# LED_INDICATORS.net
KiCad netlist of a schematic drawn in Altium Designer
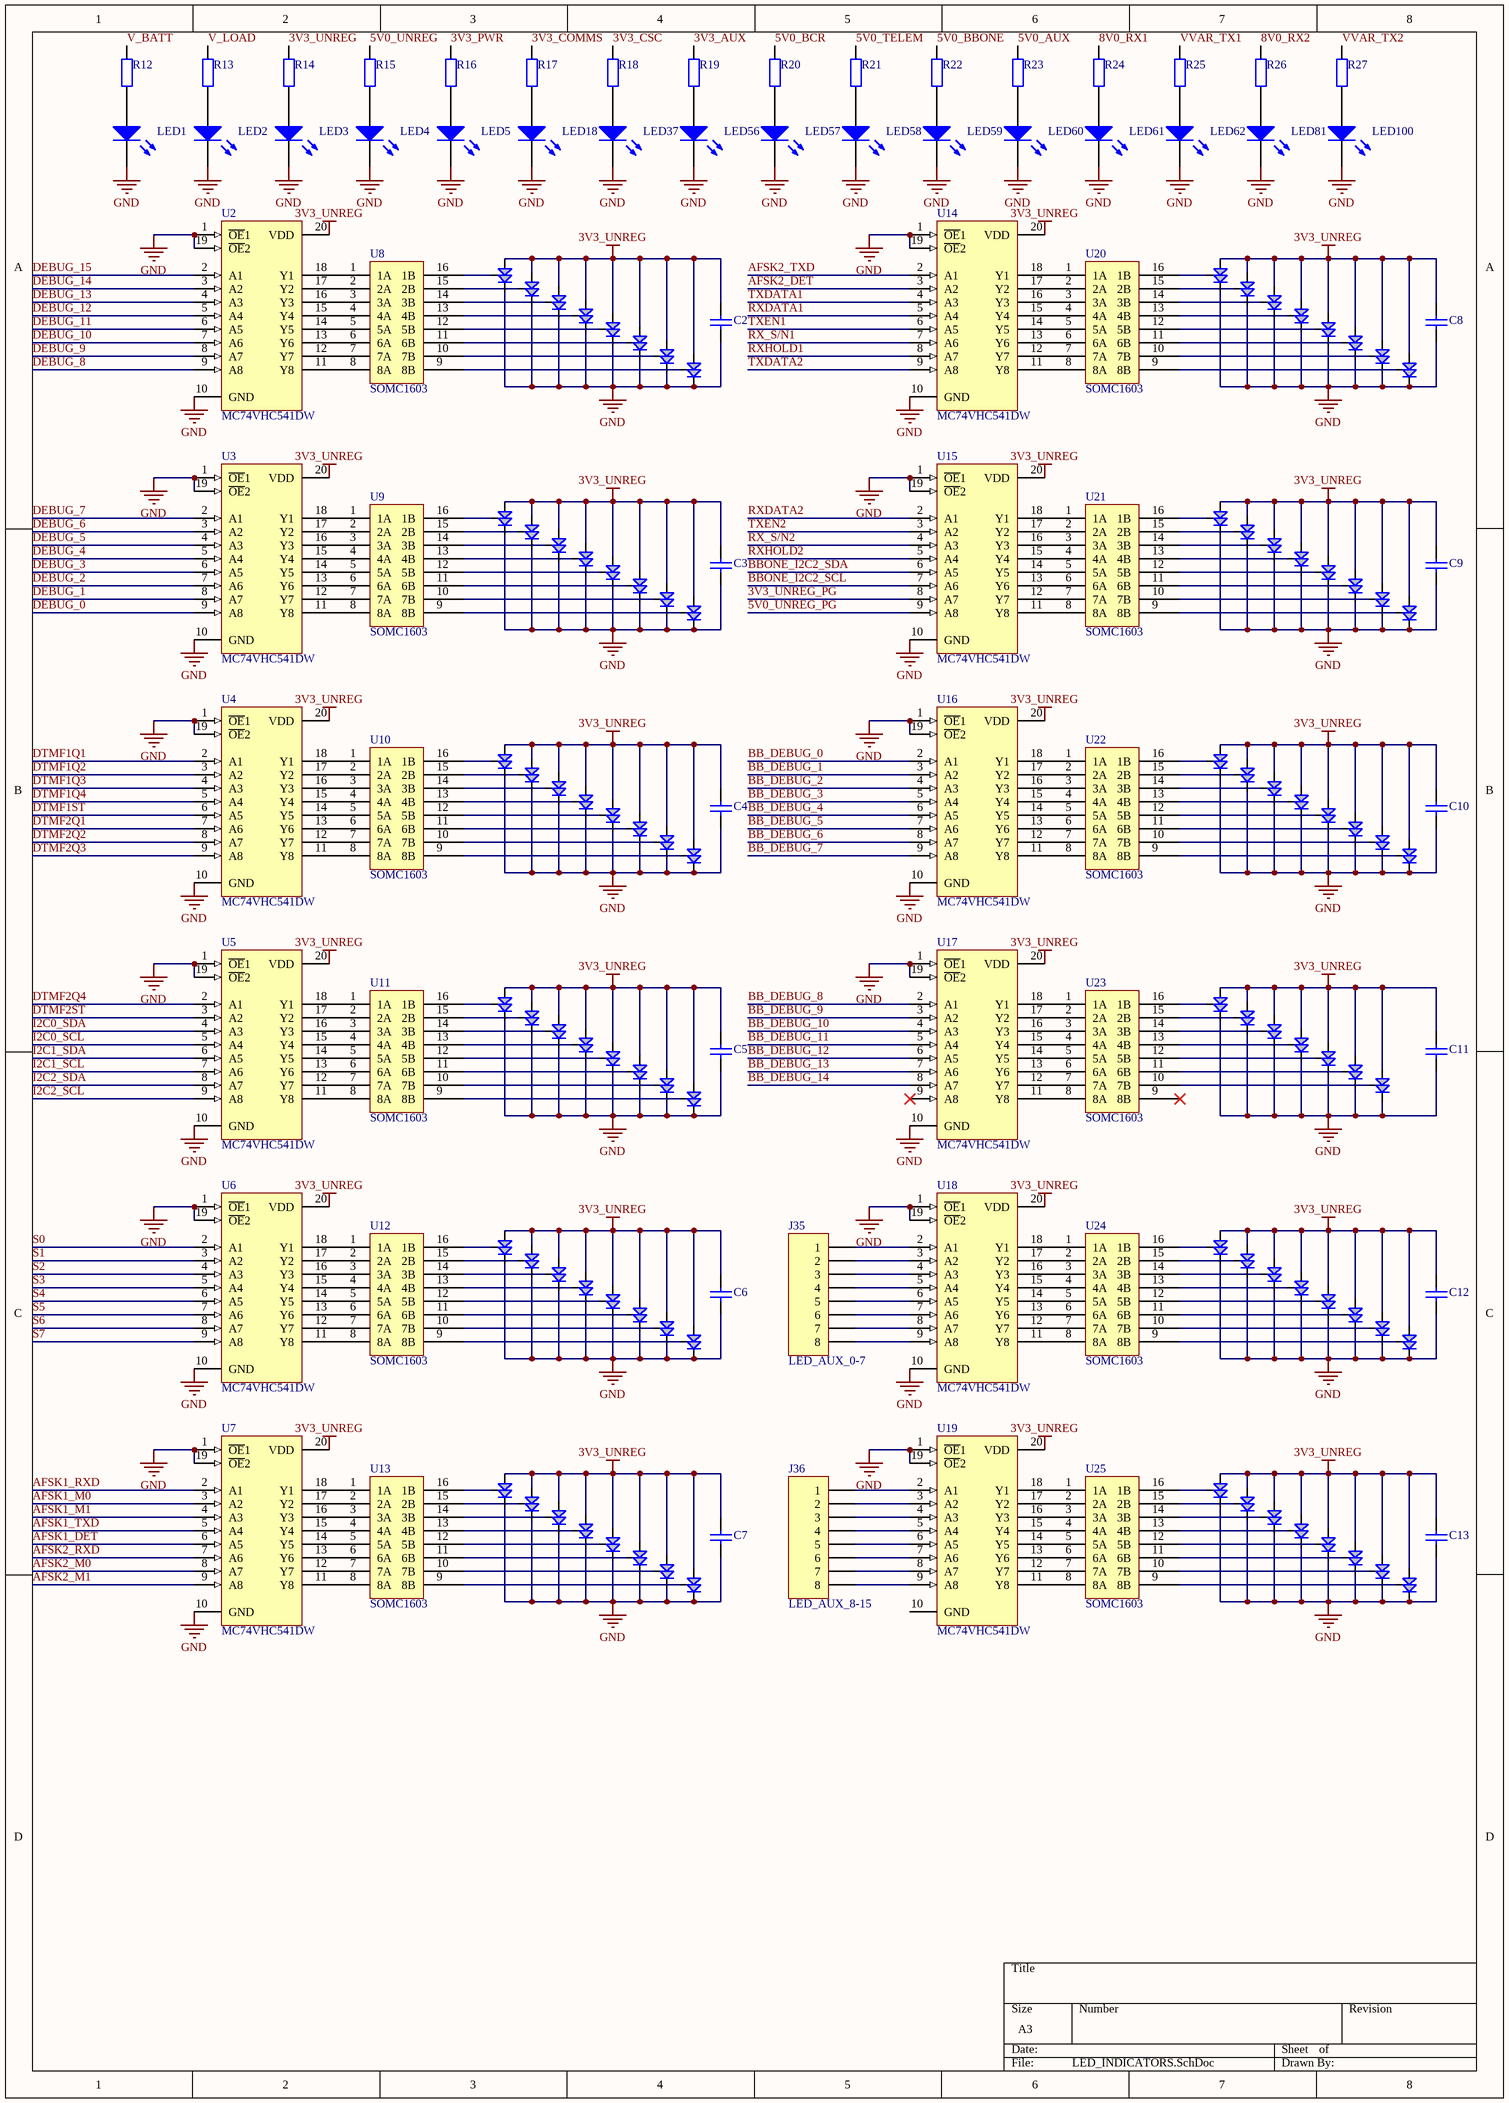
[diagram p0: LED_INDICATORS.SchDoc]

(export (version "E")
  (design (tool "Eeschema 10.0.6"))
  (components
    (comp (ref "C2")
      (value "~")
      (footprint "6-0805_M")
      (description "Capacitor")
      (fields (field (name "PUBLISHER") "Altium Limited"))
      (libsource (lib "Miscellaneous Devices") (part "Cap"))
    )
    (comp (ref "C3")
      (value "~")
      (footprint "6-0805_M")
      (description "Capacitor")
      (fields (field (name "PUBLISHER") "Altium Limited"))
      (libsource (lib "Miscellaneous Devices") (part "Cap"))
    )
    (comp (ref "C4")
      (value "~")
      (footprint "6-0805_M")
      (description "Capacitor")
      (fields (field (name "PUBLISHER") "Altium Limited"))
      (libsource (lib "Miscellaneous Devices") (part "Cap"))
    )
    (comp (ref "C5")
      (value "~")
      (footprint "6-0805_M")
      (description "Capacitor")
      (fields (field (name "PUBLISHER") "Altium Limited"))
      (libsource (lib "Miscellaneous Devices") (part "Cap"))
    )
    (comp (ref "C6")
      (value "~")
      (footprint "6-0805_M")
      (description "Capacitor")
      (fields (field (name "PUBLISHER") "Altium Limited"))
      (libsource (lib "Miscellaneous Devices") (part "Cap"))
    )
    (comp (ref "C7")
      (value "~")
      (footprint "6-0805_M")
      (description "Capacitor")
      (fields (field (name "PUBLISHER") "Altium Limited"))
      (libsource (lib "Miscellaneous Devices") (part "Cap"))
    )
    (comp (ref "C8")
      (value "~")
      (footprint "6-0805_M")
      (description "Capacitor")
      (fields (field (name "PUBLISHER") "Altium Limited"))
      (libsource (lib "Miscellaneous Devices") (part "Cap"))
    )
    (comp (ref "C9")
      (value "~")
      (footprint "6-0805_M")
      (description "Capacitor")
      (fields (field (name "PUBLISHER") "Altium Limited"))
      (libsource (lib "Miscellaneous Devices") (part "Cap"))
    )
    (comp (ref "C10")
      (value "~")
      (footprint "6-0805_M")
      (description "Capacitor")
      (fields (field (name "PUBLISHER") "Altium Limited"))
      (libsource (lib "Miscellaneous Devices") (part "Cap"))
    )
    (comp (ref "C11")
      (value "~")
      (footprint "6-0805_M")
      (description "Capacitor")
      (fields (field (name "PUBLISHER") "Altium Limited"))
      (libsource (lib "Miscellaneous Devices") (part "Cap"))
    )
    (comp (ref "C12")
      (value "~")
      (footprint "6-0805_M")
      (description "Capacitor")
      (fields (field (name "PUBLISHER") "Altium Limited"))
      (libsource (lib "Miscellaneous Devices") (part "Cap"))
    )
    (comp (ref "C13")
      (value "~")
      (footprint "6-0805_M")
      (description "Capacitor")
      (fields (field (name "PUBLISHER") "Altium Limited"))
      (libsource (lib "Miscellaneous Devices") (part "Cap"))
    )
    (comp (ref "J35")
      (value "LED_AUX_0-7")
      (footprint "HDR1X8")
      (description "Header, 8-Pin")
      (fields (field (name "PUBLISHER") "Altium Limited"))
      (libsource (lib "Miscellaneous Connectors") (part "Header 8"))
    )
    (comp (ref "J36")
      (value "LED_AUX_8-15")
      (footprint "HDR1X8")
      (description "Header, 8-Pin")
      (fields (field (name "PUBLISHER") "Altium Limited"))
      (libsource (lib "Miscellaneous Connectors") (part "Header 8"))
    )
    (comp (ref "LED1")
      (value "V_BATT")
      (footprint "6-0805_M")
      (description "Typical INFRARED GaAs LED")
      (fields (field (name "PUBLISHER") "Altium Limited"))
      (libsource (lib "Miscellaneous Devices") (part "LED0"))
    )
    (comp (ref "LED2")
      (value "V_LOAD")
      (footprint "6-0805_M")
      (description "Typical INFRARED GaAs LED")
      (fields (field (name "PUBLISHER") "Altium Limited"))
      (libsource (lib "Miscellaneous Devices") (part "LED0"))
    )
    (comp (ref "LED3")
      (value "3V3_UNREG")
      (footprint "6-0805_M")
      (description "Typical INFRARED GaAs LED")
      (fields (field (name "PUBLISHER") "Altium Limited"))
      (libsource (lib "Miscellaneous Devices") (part "LED0"))
    )
    (comp (ref "LED4")
      (value "5V0_UNREG")
      (footprint "6-0805_M")
      (description "Typical INFRARED GaAs LED")
      (fields (field (name "PUBLISHER") "Altium Limited"))
      (libsource (lib "Miscellaneous Devices") (part "LED0"))
    )
    (comp (ref "LED5")
      (value "3V3_PWR")
      (footprint "6-0805_M")
      (description "Typical INFRARED GaAs LED")
      (fields (field (name "PUBLISHER") "Altium Limited"))
      (libsource (lib "Miscellaneous Devices") (part "LED0"))
    )
    (comp (ref "LED6")
      (value "DEBUG_15")
      (footprint "BIDIRECTIONAL LED")
      (libsource (lib "FlatBoards") (part "BIDIRECTIONAL LED"))
    )
    (comp (ref "LED7")
      (value "DEBUG_7")
      (footprint "BIDIRECTIONAL LED")
      (libsource (lib "FlatBoards") (part "BIDIRECTIONAL LED"))
    )
    (comp (ref "LED8")
      (value "DTMF1Q1")
      (footprint "BIDIRECTIONAL LED")
      (libsource (lib "FlatBoards") (part "BIDIRECTIONAL LED"))
    )
    (comp (ref "LED9")
      (value "DTMF2Q4")
      (footprint "BIDIRECTIONAL LED")
      (libsource (lib "FlatBoards") (part "BIDIRECTIONAL LED"))
    )
    (comp (ref "LED10")
      (value "S0")
      (footprint "BIDIRECTIONAL LED")
      (libsource (lib "FlatBoards") (part "BIDIRECTIONAL LED"))
    )
    (comp (ref "LED11")
      (value "AFSK1_RXD")
      (footprint "BIDIRECTIONAL LED")
      (libsource (lib "FlatBoards") (part "BIDIRECTIONAL LED"))
    )
    (comp (ref "LED12")
      (value "DEBUG_14")
      (footprint "BIDIRECTIONAL LED")
      (libsource (lib "FlatBoards") (part "BIDIRECTIONAL LED"))
    )
    (comp (ref "LED13")
      (value "DEBUG_6")
      (footprint "BIDIRECTIONAL LED")
      (libsource (lib "FlatBoards") (part "BIDIRECTIONAL LED"))
    )
    (comp (ref "LED14")
      (value "DTMF1Q2")
      (footprint "BIDIRECTIONAL LED")
      (libsource (lib "FlatBoards") (part "BIDIRECTIONAL LED"))
    )
    (comp (ref "LED15")
      (value "DTMF2ST")
      (footprint "BIDIRECTIONAL LED")
      (libsource (lib "FlatBoards") (part "BIDIRECTIONAL LED"))
    )
    (comp (ref "LED16")
      (value "S1")
      (footprint "BIDIRECTIONAL LED")
      (libsource (lib "FlatBoards") (part "BIDIRECTIONAL LED"))
    )
    (comp (ref "LED17")
      (value "AFSK1_M0")
      (footprint "BIDIRECTIONAL LED")
      (libsource (lib "FlatBoards") (part "BIDIRECTIONAL LED"))
    )
    (comp (ref "LED18")
      (value "3V3_COMMS")
      (footprint "6-0805_M")
      (description "Typical INFRARED GaAs LED")
      (fields (field (name "PUBLISHER") "Altium Limited"))
      (libsource (lib "Miscellaneous Devices") (part "LED0"))
    )
    (comp (ref "LED19")
      (value "DEBUG_13")
      (footprint "BIDIRECTIONAL LED")
      (libsource (lib "FlatBoards") (part "BIDIRECTIONAL LED"))
    )
    (comp (ref "LED20")
      (value "DEBUG_5")
      (footprint "BIDIRECTIONAL LED")
      (libsource (lib "FlatBoards") (part "BIDIRECTIONAL LED"))
    )
    (comp (ref "LED21")
      (value "DTMF1Q3")
      (footprint "BIDIRECTIONAL LED")
      (libsource (lib "FlatBoards") (part "BIDIRECTIONAL LED"))
    )
    (comp (ref "LED22")
      (value "I2C0_SDA")
      (footprint "BIDIRECTIONAL LED")
      (libsource (lib "FlatBoards") (part "BIDIRECTIONAL LED"))
    )
    (comp (ref "LED23")
      (value "S2")
      (footprint "BIDIRECTIONAL LED")
      (libsource (lib "FlatBoards") (part "BIDIRECTIONAL LED"))
    )
    (comp (ref "LED24")
      (value "AFSK1_M1")
      (footprint "BIDIRECTIONAL LED")
      (libsource (lib "FlatBoards") (part "BIDIRECTIONAL LED"))
    )
    (comp (ref "LED25")
      (value "DEBUG_12")
      (footprint "BIDIRECTIONAL LED")
      (libsource (lib "FlatBoards") (part "BIDIRECTIONAL LED"))
    )
    (comp (ref "LED26")
      (value "DEBUG_4")
      (footprint "BIDIRECTIONAL LED")
      (libsource (lib "FlatBoards") (part "BIDIRECTIONAL LED"))
    )
    (comp (ref "LED27")
      (value "DTMF1Q4")
      (footprint "BIDIRECTIONAL LED")
      (libsource (lib "FlatBoards") (part "BIDIRECTIONAL LED"))
    )
    (comp (ref "LED28")
      (value "I2C0_SCL")
      (footprint "BIDIRECTIONAL LED")
      (libsource (lib "FlatBoards") (part "BIDIRECTIONAL LED"))
    )
    (comp (ref "LED29")
      (value "S3")
      (footprint "BIDIRECTIONAL LED")
      (libsource (lib "FlatBoards") (part "BIDIRECTIONAL LED"))
    )
    (comp (ref "LED30")
      (value "AFSK1_TXD")
      (footprint "BIDIRECTIONAL LED")
      (libsource (lib "FlatBoards") (part "BIDIRECTIONAL LED"))
    )
    (comp (ref "LED31")
      (value "DEBUG_11")
      (footprint "BIDIRECTIONAL LED")
      (libsource (lib "FlatBoards") (part "BIDIRECTIONAL LED"))
    )
    (comp (ref "LED32")
      (value "DEBUG_3")
      (footprint "BIDIRECTIONAL LED")
      (libsource (lib "FlatBoards") (part "BIDIRECTIONAL LED"))
    )
    (comp (ref "LED33")
      (value "DTMF1ST")
      (footprint "BIDIRECTIONAL LED")
      (libsource (lib "FlatBoards") (part "BIDIRECTIONAL LED"))
    )
    (comp (ref "LED34")
      (value "I2C1_SDA")
      (footprint "BIDIRECTIONAL LED")
      (libsource (lib "FlatBoards") (part "BIDIRECTIONAL LED"))
    )
    (comp (ref "LED35")
      (value "S4")
      (footprint "BIDIRECTIONAL LED")
      (libsource (lib "FlatBoards") (part "BIDIRECTIONAL LED"))
    )
    (comp (ref "LED36")
      (value "AFSK1_DET")
      (footprint "BIDIRECTIONAL LED")
      (libsource (lib "FlatBoards") (part "BIDIRECTIONAL LED"))
    )
    (comp (ref "LED37")
      (value "3V3_CSC")
      (footprint "6-0805_M")
      (description "Typical INFRARED GaAs LED")
      (fields (field (name "PUBLISHER") "Altium Limited"))
      (libsource (lib "Miscellaneous Devices") (part "LED0"))
    )
    (comp (ref "LED38")
      (value "DEBUG_10")
      (footprint "BIDIRECTIONAL LED")
      (libsource (lib "FlatBoards") (part "BIDIRECTIONAL LED"))
    )
    (comp (ref "LED39")
      (value "DEBUG_2")
      (footprint "BIDIRECTIONAL LED")
      (libsource (lib "FlatBoards") (part "BIDIRECTIONAL LED"))
    )
    (comp (ref "LED40")
      (value "DTMF2Q1")
      (footprint "BIDIRECTIONAL LED")
      (libsource (lib "FlatBoards") (part "BIDIRECTIONAL LED"))
    )
    (comp (ref "LED41")
      (value "I2C1_SCL")
      (footprint "BIDIRECTIONAL LED")
      (libsource (lib "FlatBoards") (part "BIDIRECTIONAL LED"))
    )
    (comp (ref "LED42")
      (value "S5")
      (footprint "BIDIRECTIONAL LED")
      (libsource (lib "FlatBoards") (part "BIDIRECTIONAL LED"))
    )
    (comp (ref "LED43")
      (value "AFSK2_RXD")
      (footprint "BIDIRECTIONAL LED")
      (libsource (lib "FlatBoards") (part "BIDIRECTIONAL LED"))
    )
    (comp (ref "LED44")
      (value "DEBUG_9")
      (footprint "BIDIRECTIONAL LED")
      (libsource (lib "FlatBoards") (part "BIDIRECTIONAL LED"))
    )
    (comp (ref "LED45")
      (value "DEBUG_1")
      (footprint "BIDIRECTIONAL LED")
      (libsource (lib "FlatBoards") (part "BIDIRECTIONAL LED"))
    )
    (comp (ref "LED46")
      (value "DTMF2Q2")
      (footprint "BIDIRECTIONAL LED")
      (libsource (lib "FlatBoards") (part "BIDIRECTIONAL LED"))
    )
    (comp (ref "LED47")
      (value "I2C2_SDA")
      (footprint "BIDIRECTIONAL LED")
      (libsource (lib "FlatBoards") (part "BIDIRECTIONAL LED"))
    )
    (comp (ref "LED48")
      (value "S6")
      (footprint "BIDIRECTIONAL LED")
      (libsource (lib "FlatBoards") (part "BIDIRECTIONAL LED"))
    )
    (comp (ref "LED49")
      (value "AFSK2_M0")
      (footprint "BIDIRECTIONAL LED")
      (libsource (lib "FlatBoards") (part "BIDIRECTIONAL LED"))
    )
    (comp (ref "LED50")
      (value "DEBUG_8")
      (footprint "BIDIRECTIONAL LED")
      (libsource (lib "FlatBoards") (part "BIDIRECTIONAL LED"))
    )
    (comp (ref "LED51")
      (value "DEBUG_0")
      (footprint "BIDIRECTIONAL LED")
      (libsource (lib "FlatBoards") (part "BIDIRECTIONAL LED"))
    )
    (comp (ref "LED52")
      (value "DTMF2Q3")
      (footprint "BIDIRECTIONAL LED")
      (libsource (lib "FlatBoards") (part "BIDIRECTIONAL LED"))
    )
    (comp (ref "LED53")
      (value "I2C2_SCL")
      (footprint "BIDIRECTIONAL LED")
      (libsource (lib "FlatBoards") (part "BIDIRECTIONAL LED"))
    )
    (comp (ref "LED54")
      (value "S7")
      (footprint "BIDIRECTIONAL LED")
      (libsource (lib "FlatBoards") (part "BIDIRECTIONAL LED"))
    )
    (comp (ref "LED55")
      (value "AFSK2_M1")
      (footprint "BIDIRECTIONAL LED")
      (libsource (lib "FlatBoards") (part "BIDIRECTIONAL LED"))
    )
    (comp (ref "LED56")
      (value "3V3_AUX")
      (footprint "6-0805_M")
      (description "Typical INFRARED GaAs LED")
      (fields (field (name "PUBLISHER") "Altium Limited"))
      (libsource (lib "Miscellaneous Devices") (part "LED0"))
    )
    (comp (ref "LED57")
      (value "5V0_BCR")
      (footprint "6-0805_M")
      (description "Typical INFRARED GaAs LED")
      (fields (field (name "PUBLISHER") "Altium Limited"))
      (libsource (lib "Miscellaneous Devices") (part "LED0"))
    )
    (comp (ref "LED58")
      (value "5V0_TELEM")
      (footprint "6-0805_M")
      (description "Typical INFRARED GaAs LED")
      (fields (field (name "PUBLISHER") "Altium Limited"))
      (libsource (lib "Miscellaneous Devices") (part "LED0"))
    )
    (comp (ref "LED59")
      (value "5V0_BBONE")
      (footprint "6-0805_M")
      (description "Typical INFRARED GaAs LED")
      (fields (field (name "PUBLISHER") "Altium Limited"))
      (libsource (lib "Miscellaneous Devices") (part "LED0"))
    )
    (comp (ref "LED60")
      (value "5V0_AUX")
      (footprint "6-0805_M")
      (description "Typical INFRARED GaAs LED")
      (fields (field (name "PUBLISHER") "Altium Limited"))
      (libsource (lib "Miscellaneous Devices") (part "LED0"))
    )
    (comp (ref "LED61")
      (value "8V0_RX1")
      (footprint "6-0805_M")
      (description "Typical INFRARED GaAs LED")
      (fields (field (name "PUBLISHER") "Altium Limited"))
      (libsource (lib "Miscellaneous Devices") (part "LED0"))
    )
    (comp (ref "LED62")
      (value "VVAR_TX1")
      (footprint "6-0805_M")
      (description "Typical INFRARED GaAs LED")
      (fields (field (name "PUBLISHER") "Altium Limited"))
      (libsource (lib "Miscellaneous Devices") (part "LED0"))
    )
    (comp (ref "LED63")
      (value "AFSK2_TXD")
      (footprint "BIDIRECTIONAL LED")
      (libsource (lib "FlatBoards") (part "BIDIRECTIONAL LED"))
    )
    (comp (ref "LED64")
      (value "RXDATA2")
      (footprint "BIDIRECTIONAL LED")
      (libsource (lib "FlatBoards") (part "BIDIRECTIONAL LED"))
    )
    (comp (ref "LED65")
      (value "BB_DEBUG_0")
      (footprint "BIDIRECTIONAL LED")
      (libsource (lib "FlatBoards") (part "BIDIRECTIONAL LED"))
    )
    (comp (ref "LED66")
      (value "BB_DEBUG_8")
      (footprint "BIDIRECTIONAL LED")
      (libsource (lib "FlatBoards") (part "BIDIRECTIONAL LED"))
    )
    (comp (ref "LED67")
      (value "LED_AUX_0")
      (footprint "BIDIRECTIONAL LED")
      (libsource (lib "FlatBoards") (part "BIDIRECTIONAL LED"))
    )
    (comp (ref "LED68")
      (value "LED_AUX_8")
      (footprint "BIDIRECTIONAL LED")
      (libsource (lib "FlatBoards") (part "BIDIRECTIONAL LED"))
    )
    (comp (ref "LED69")
      (value "AFSK2_DET")
      (footprint "BIDIRECTIONAL LED")
      (libsource (lib "FlatBoards") (part "BIDIRECTIONAL LED"))
    )
    (comp (ref "LED70")
      (value "TXEN2")
      (footprint "BIDIRECTIONAL LED")
      (libsource (lib "FlatBoards") (part "BIDIRECTIONAL LED"))
    )
    (comp (ref "LED71")
      (value "BB_DEBUG_1")
      (footprint "BIDIRECTIONAL LED")
      (libsource (lib "FlatBoards") (part "BIDIRECTIONAL LED"))
    )
    (comp (ref "LED72")
      (value "BB_DEBUG_9")
      (footprint "BIDIRECTIONAL LED")
      (libsource (lib "FlatBoards") (part "BIDIRECTIONAL LED"))
    )
    (comp (ref "LED73")
      (value "LED_AUX_1")
      (footprint "BIDIRECTIONAL LED")
      (libsource (lib "FlatBoards") (part "BIDIRECTIONAL LED"))
    )
    (comp (ref "LED74")
      (value "LED_AUX_9")
      (footprint "BIDIRECTIONAL LED")
      (libsource (lib "FlatBoards") (part "BIDIRECTIONAL LED"))
    )
    (comp (ref "LED75")
      (value "TXDATA1")
      (footprint "BIDIRECTIONAL LED")
      (libsource (lib "FlatBoards") (part "BIDIRECTIONAL LED"))
    )
    (comp (ref "LED76")
      (value "RX_S/N2")
      (footprint "BIDIRECTIONAL LED")
      (libsource (lib "FlatBoards") (part "BIDIRECTIONAL LED"))
    )
    (comp (ref "LED77")
      (value "BB_DEBUG_2")
      (footprint "BIDIRECTIONAL LED")
      (libsource (lib "FlatBoards") (part "BIDIRECTIONAL LED"))
    )
    (comp (ref "LED78")
      (value "BB_DEBUG_10")
      (footprint "BIDIRECTIONAL LED")
      (libsource (lib "FlatBoards") (part "BIDIRECTIONAL LED"))
    )
    (comp (ref "LED79")
      (value "LED_AUX_2")
      (footprint "BIDIRECTIONAL LED")
      (libsource (lib "FlatBoards") (part "BIDIRECTIONAL LED"))
    )
    (comp (ref "LED80")
      (value "LED_AUX_10")
      (footprint "BIDIRECTIONAL LED")
      (libsource (lib "FlatBoards") (part "BIDIRECTIONAL LED"))
    )
    (comp (ref "LED81")
      (value "8V0_RX2")
      (footprint "6-0805_M")
      (description "Typical INFRARED GaAs LED")
      (fields (field (name "PUBLISHER") "Altium Limited"))
      (libsource (lib "Miscellaneous Devices") (part "LED0"))
    )
    (comp (ref "LED82")
      (value "RXDATA1")
      (footprint "BIDIRECTIONAL LED")
      (libsource (lib "FlatBoards") (part "BIDIRECTIONAL LED"))
    )
    (comp (ref "LED83")
      (value "RXHOLD2")
      (footprint "BIDIRECTIONAL LED")
      (libsource (lib "FlatBoards") (part "BIDIRECTIONAL LED"))
    )
    (comp (ref "LED84")
      (value "BB_DEBUG_3")
      (footprint "BIDIRECTIONAL LED")
      (libsource (lib "FlatBoards") (part "BIDIRECTIONAL LED"))
    )
    (comp (ref "LED85")
      (value "BB_DEBUG_11")
      (footprint "BIDIRECTIONAL LED")
      (libsource (lib "FlatBoards") (part "BIDIRECTIONAL LED"))
    )
    (comp (ref "LED86")
      (value "LED_AUX_3")
      (footprint "BIDIRECTIONAL LED")
      (libsource (lib "FlatBoards") (part "BIDIRECTIONAL LED"))
    )
    (comp (ref "LED87")
      (value "LED_AUX_11")
      (footprint "BIDIRECTIONAL LED")
      (libsource (lib "FlatBoards") (part "BIDIRECTIONAL LED"))
    )
    (comp (ref "LED88")
      (value "TXEN1")
      (footprint "BIDIRECTIONAL LED")
      (libsource (lib "FlatBoards") (part "BIDIRECTIONAL LED"))
    )
    (comp (ref "LED89")
      (value "BBONE_I2C2_SDA")
      (footprint "BIDIRECTIONAL LED")
      (libsource (lib "FlatBoards") (part "BIDIRECTIONAL LED"))
    )
    (comp (ref "LED90")
      (value "BB_DEBUG_4")
      (footprint "BIDIRECTIONAL LED")
      (libsource (lib "FlatBoards") (part "BIDIRECTIONAL LED"))
    )
    (comp (ref "LED91")
      (value "BB_DEBUG_12")
      (footprint "BIDIRECTIONAL LED")
      (libsource (lib "FlatBoards") (part "BIDIRECTIONAL LED"))
    )
    (comp (ref "LED92")
      (value "LED_AUX_4")
      (footprint "BIDIRECTIONAL LED")
      (libsource (lib "FlatBoards") (part "BIDIRECTIONAL LED"))
    )
    (comp (ref "LED93")
      (value "LED_AUX_12")
      (footprint "BIDIRECTIONAL LED")
      (libsource (lib "FlatBoards") (part "BIDIRECTIONAL LED"))
    )
    (comp (ref "LED94")
      (value "RX_S/N1")
      (footprint "BIDIRECTIONAL LED")
      (libsource (lib "FlatBoards") (part "BIDIRECTIONAL LED"))
    )
    (comp (ref "LED95")
      (value "BBONE_I2C2_SCL")
      (footprint "BIDIRECTIONAL LED")
      (libsource (lib "FlatBoards") (part "BIDIRECTIONAL LED"))
    )
    (comp (ref "LED96")
      (value "BB_DEBUG_5")
      (footprint "BIDIRECTIONAL LED")
      (libsource (lib "FlatBoards") (part "BIDIRECTIONAL LED"))
    )
    (comp (ref "LED97")
      (value "BB_DEBUG_13")
      (footprint "BIDIRECTIONAL LED")
      (libsource (lib "FlatBoards") (part "BIDIRECTIONAL LED"))
    )
    (comp (ref "LED98")
      (value "LED_AUX_5")
      (footprint "BIDIRECTIONAL LED")
      (libsource (lib "FlatBoards") (part "BIDIRECTIONAL LED"))
    )
    (comp (ref "LED99")
      (value "LED_AUX_13")
      (footprint "BIDIRECTIONAL LED")
      (libsource (lib "FlatBoards") (part "BIDIRECTIONAL LED"))
    )
    (comp (ref "LED100")
      (value "VVAR_TX2")
      (footprint "6-0805_M")
      (description "Typical INFRARED GaAs LED")
      (fields (field (name "PUBLISHER") "Altium Limited"))
      (libsource (lib "Miscellaneous Devices") (part "LED0"))
    )
    (comp (ref "LED101")
      (value "RXHOLD1")
      (footprint "BIDIRECTIONAL LED")
      (libsource (lib "FlatBoards") (part "BIDIRECTIONAL LED"))
    )
    (comp (ref "LED102")
      (value "3V3_UNREG_PG")
      (footprint "BIDIRECTIONAL LED")
      (libsource (lib "FlatBoards") (part "BIDIRECTIONAL LED"))
    )
    (comp (ref "LED103")
      (value "BB_DEBUG_6")
      (footprint "BIDIRECTIONAL LED")
      (libsource (lib "FlatBoards") (part "BIDIRECTIONAL LED"))
    )
    (comp (ref "LED104")
      (value "BB_DEBUG_14")
      (footprint "BIDIRECTIONAL LED")
      (libsource (lib "FlatBoards") (part "BIDIRECTIONAL LED"))
    )
    (comp (ref "LED105")
      (value "LED_AUX_6")
      (footprint "BIDIRECTIONAL LED")
      (libsource (lib "FlatBoards") (part "BIDIRECTIONAL LED"))
    )
    (comp (ref "LED106")
      (value "LED_AUX_14")
      (footprint "BIDIRECTIONAL LED")
      (libsource (lib "FlatBoards") (part "BIDIRECTIONAL LED"))
    )
    (comp (ref "LED107")
      (value "TXDATA2")
      (footprint "BIDIRECTIONAL LED")
      (libsource (lib "FlatBoards") (part "BIDIRECTIONAL LED"))
    )
    (comp (ref "LED108")
      (value "5V0_UNREG_PG")
      (footprint "BIDIRECTIONAL LED")
      (libsource (lib "FlatBoards") (part "BIDIRECTIONAL LED"))
    )
    (comp (ref "LED109")
      (value "BB_DEBUG_7")
      (footprint "BIDIRECTIONAL LED")
      (libsource (lib "FlatBoards") (part "BIDIRECTIONAL LED"))
    )
    (comp (ref "LED111")
      (value "LED_AUX_7")
      (footprint "BIDIRECTIONAL LED")
      (libsource (lib "FlatBoards") (part "BIDIRECTIONAL LED"))
    )
    (comp (ref "LED112")
      (value "LED_AUX_15")
      (footprint "BIDIRECTIONAL LED")
      (libsource (lib "FlatBoards") (part "BIDIRECTIONAL LED"))
    )
    (comp (ref "R12")
      (value "Res2")
      (footprint "6-0805_M")
      (description "Resistor")
      (fields (field (name "PUBLISHER") "Altium Limited"))
      (libsource (lib "Miscellaneous Devices") (part "Res2"))
    )
    (comp (ref "R13")
      (value "Res2")
      (footprint "6-0805_M")
      (description "Resistor")
      (fields (field (name "PUBLISHER") "Altium Limited"))
      (libsource (lib "Miscellaneous Devices") (part "Res2"))
    )
    (comp (ref "R14")
      (value "Res2")
      (footprint "6-0805_M")
      (description "Resistor")
      (fields (field (name "PUBLISHER") "Altium Limited"))
      (libsource (lib "Miscellaneous Devices") (part "Res2"))
    )
    (comp (ref "R15")
      (value "Res2")
      (footprint "6-0805_M")
      (description "Resistor")
      (fields (field (name "PUBLISHER") "Altium Limited"))
      (libsource (lib "Miscellaneous Devices") (part "Res2"))
    )
    (comp (ref "R16")
      (value "Res2")
      (footprint "6-0805_M")
      (description "Resistor")
      (fields (field (name "PUBLISHER") "Altium Limited"))
      (libsource (lib "Miscellaneous Devices") (part "Res2"))
    )
    (comp (ref "R17")
      (value "Res2")
      (footprint "6-0805_M")
      (description "Resistor")
      (fields (field (name "PUBLISHER") "Altium Limited"))
      (libsource (lib "Miscellaneous Devices") (part "Res2"))
    )
    (comp (ref "R18")
      (value "Res2")
      (footprint "6-0805_M")
      (description "Resistor")
      (fields (field (name "PUBLISHER") "Altium Limited"))
      (libsource (lib "Miscellaneous Devices") (part "Res2"))
    )
    (comp (ref "R19")
      (value "Res2")
      (footprint "6-0805_M")
      (description "Resistor")
      (fields (field (name "PUBLISHER") "Altium Limited"))
      (libsource (lib "Miscellaneous Devices") (part "Res2"))
    )
    (comp (ref "R20")
      (value "Res2")
      (footprint "6-0805_M")
      (description "Resistor")
      (fields (field (name "PUBLISHER") "Altium Limited"))
      (libsource (lib "Miscellaneous Devices") (part "Res2"))
    )
    (comp (ref "R21")
      (value "Res2")
      (footprint "6-0805_M")
      (description "Resistor")
      (fields (field (name "PUBLISHER") "Altium Limited"))
      (libsource (lib "Miscellaneous Devices") (part "Res2"))
    )
    (comp (ref "R22")
      (value "Res2")
      (footprint "6-0805_M")
      (description "Resistor")
      (fields (field (name "PUBLISHER") "Altium Limited"))
      (libsource (lib "Miscellaneous Devices") (part "Res2"))
    )
    (comp (ref "R23")
      (value "Res2")
      (footprint "6-0805_M")
      (description "Resistor")
      (fields (field (name "PUBLISHER") "Altium Limited"))
      (libsource (lib "Miscellaneous Devices") (part "Res2"))
    )
    (comp (ref "R24")
      (value "Res2")
      (footprint "6-0805_M")
      (description "Resistor")
      (fields (field (name "PUBLISHER") "Altium Limited"))
      (libsource (lib "Miscellaneous Devices") (part "Res2"))
    )
    (comp (ref "R25")
      (value "Res2")
      (footprint "6-0805_M")
      (description "Resistor")
      (fields (field (name "PUBLISHER") "Altium Limited"))
      (libsource (lib "Miscellaneous Devices") (part "Res2"))
    )
    (comp (ref "R26")
      (value "Res2")
      (footprint "6-0805_M")
      (description "Resistor")
      (fields (field (name "PUBLISHER") "Altium Limited"))
      (libsource (lib "Miscellaneous Devices") (part "Res2"))
    )
    (comp (ref "R27")
      (value "Res2")
      (footprint "6-0805_M")
      (description "Resistor")
      (fields (field (name "PUBLISHER") "Altium Limited"))
      (libsource (lib "Miscellaneous Devices") (part "Res2"))
    )
    (comp (ref "U2")
      (value "MC74VHC541DW")
      (footprint "751D-04_M")
      (description "Octal Bus Buffer")
      (fields (field (name "PUBLISHER") "Altium Limited"))
      (libsource (lib "FlatBoards") (part "MC74VHC541DW"))
    )
    (comp (ref "U3")
      (value "MC74VHC541DW")
      (footprint "751D-04_M")
      (description "Octal Bus Buffer")
      (fields (field (name "PUBLISHER") "Altium Limited"))
      (libsource (lib "FlatBoards") (part "MC74VHC541DW"))
    )
    (comp (ref "U4")
      (value "MC74VHC541DW")
      (footprint "751D-04_M")
      (description "Octal Bus Buffer")
      (fields (field (name "PUBLISHER") "Altium Limited"))
      (libsource (lib "FlatBoards") (part "MC74VHC541DW"))
    )
    (comp (ref "U5")
      (value "MC74VHC541DW")
      (footprint "751D-04_M")
      (description "Octal Bus Buffer")
      (fields (field (name "PUBLISHER") "Altium Limited"))
      (libsource (lib "FlatBoards") (part "MC74VHC541DW"))
    )
    (comp (ref "U6")
      (value "MC74VHC541DW")
      (footprint "751D-04_M")
      (description "Octal Bus Buffer")
      (fields (field (name "PUBLISHER") "Altium Limited"))
      (libsource (lib "FlatBoards") (part "MC74VHC541DW"))
    )
    (comp (ref "U7")
      (value "MC74VHC541DW")
      (footprint "751D-04_M")
      (description "Octal Bus Buffer")
      (fields (field (name "PUBLISHER") "Altium Limited"))
      (libsource (lib "FlatBoards") (part "MC74VHC541DW"))
    )
    (comp (ref "U8")
      (value "SOMC1603")
      (footprint "SOMC1603")
      (libsource (lib "FlatBoards") (part "SOMC1603"))
    )
    (comp (ref "U9")
      (value "SOMC1603")
      (footprint "SOMC1603")
      (libsource (lib "FlatBoards") (part "SOMC1603"))
    )
    (comp (ref "U10")
      (value "SOMC1603")
      (footprint "SOMC1603")
      (libsource (lib "FlatBoards") (part "SOMC1603"))
    )
    (comp (ref "U11")
      (value "SOMC1603")
      (footprint "SOMC1603")
      (libsource (lib "FlatBoards") (part "SOMC1603"))
    )
    (comp (ref "U12")
      (value "SOMC1603")
      (footprint "SOMC1603")
      (libsource (lib "FlatBoards") (part "SOMC1603"))
    )
    (comp (ref "U13")
      (value "SOMC1603")
      (footprint "SOMC1603")
      (libsource (lib "FlatBoards") (part "SOMC1603"))
    )
    (comp (ref "U14")
      (value "MC74VHC541DW")
      (footprint "751D-04_M")
      (description "Octal Bus Buffer")
      (fields (field (name "PUBLISHER") "Altium Limited"))
      (libsource (lib "FlatBoards") (part "MC74VHC541DW"))
    )
    (comp (ref "U15")
      (value "MC74VHC541DW")
      (footprint "751D-04_M")
      (description "Octal Bus Buffer")
      (fields (field (name "PUBLISHER") "Altium Limited"))
      (libsource (lib "FlatBoards") (part "MC74VHC541DW"))
    )
    (comp (ref "U16")
      (value "MC74VHC541DW")
      (footprint "751D-04_M")
      (description "Octal Bus Buffer")
      (fields (field (name "PUBLISHER") "Altium Limited"))
      (libsource (lib "FlatBoards") (part "MC74VHC541DW"))
    )
    (comp (ref "U17")
      (value "MC74VHC541DW")
      (footprint "751D-04_M")
      (description "Octal Bus Buffer")
      (fields (field (name "PUBLISHER") "Altium Limited"))
      (libsource (lib "FlatBoards") (part "MC74VHC541DW"))
    )
    (comp (ref "U18")
      (value "MC74VHC541DW")
      (footprint "751D-04_M")
      (description "Octal Bus Buffer")
      (fields (field (name "PUBLISHER") "Altium Limited"))
      (libsource (lib "FlatBoards") (part "MC74VHC541DW"))
    )
    (comp (ref "U19")
      (value "MC74VHC541DW")
      (footprint "751D-04_M")
      (description "Octal Bus Buffer")
      (fields (field (name "PUBLISHER") "Altium Limited"))
      (libsource (lib "FlatBoards") (part "MC74VHC541DW"))
    )
    (comp (ref "U20")
      (value "SOMC1603")
      (footprint "SOMC1603")
      (libsource (lib "FlatBoards") (part "SOMC1603"))
    )
    (comp (ref "U21")
      (value "SOMC1603")
      (footprint "SOMC1603")
      (libsource (lib "FlatBoards") (part "SOMC1603"))
    )
    (comp (ref "U22")
      (value "SOMC1603")
      (footprint "SOMC1603")
      (libsource (lib "FlatBoards") (part "SOMC1603"))
    )
    (comp (ref "U23")
      (value "SOMC1603")
      (footprint "SOMC1603")
      (libsource (lib "FlatBoards") (part "SOMC1603"))
    )
    (comp (ref "U24")
      (value "SOMC1603")
      (footprint "SOMC1603")
      (libsource (lib "FlatBoards") (part "SOMC1603"))
    )
    (comp (ref "U25")
      (value "SOMC1603")
      (footprint "SOMC1603")
      (libsource (lib "FlatBoards") (part "SOMC1603"))
    )
  )
  (nets
    (net (code "1") (name "/3V3_AUX") (class "Default")
      (node (ref "R19") (pin "2") (pinfunction "2_2") (pintype "passive"))
    )
    (net (code "2") (name "/3V3_COMMS") (class "Default")
      (node (ref "R17") (pin "2") (pinfunction "2_2") (pintype "passive"))
    )
    (net (code "3") (name "/3V3_CSC") (class "Default")
      (node (ref "R18") (pin "2") (pinfunction "2_2") (pintype "passive"))
    )
    (net (code "4") (name "/3V3_PWR") (class "Default")
      (node (ref "R16") (pin "2") (pinfunction "2_2") (pintype "passive"))
    )
    (net (code "5") (name "/3V3_UNREG_PG") (class "Default")
      (node (ref "U15") (pin "8") (pinfunction "A7_8") (pintype "input"))
    )
    (net (code "6") (name "/5V0_AUX") (class "Default")
      (node (ref "R23") (pin "2") (pinfunction "2_2") (pintype "passive"))
    )
    (net (code "7") (name "/5V0_BBONE") (class "Default")
      (node (ref "R22") (pin "2") (pinfunction "2_2") (pintype "passive"))
    )
    (net (code "8") (name "/5V0_BCR") (class "Default")
      (node (ref "R20") (pin "2") (pinfunction "2_2") (pintype "passive"))
    )
    (net (code "9") (name "/5V0_TELEM") (class "Default")
      (node (ref "R21") (pin "2") (pinfunction "2_2") (pintype "passive"))
    )
    (net (code "10") (name "/5V0_UNREG") (class "Default")
      (node (ref "R15") (pin "2") (pinfunction "2_2") (pintype "passive"))
    )
    (net (code "11") (name "/5V0_UNREG_PG") (class "Default")
      (node (ref "U15") (pin "9") (pinfunction "A8_9") (pintype "input"))
    )
    (net (code "12") (name "/8V0_RX1") (class "Default")
      (node (ref "R24") (pin "2") (pinfunction "2_2") (pintype "passive"))
    )
    (net (code "13") (name "/8V0_RX2") (class "Default")
      (node (ref "R26") (pin "2") (pinfunction "2_2") (pintype "passive"))
    )
    (net (code "14") (name "/AFSK1_DET") (class "Default")
      (node (ref "U7") (pin "6") (pinfunction "A5_6") (pintype "input"))
    )
    (net (code "15") (name "/AFSK1_M0") (class "Default")
      (node (ref "U7") (pin "3") (pinfunction "A2_3") (pintype "input"))
    )
    (net (code "16") (name "/AFSK1_M1") (class "Default")
      (node (ref "U7") (pin "4") (pinfunction "A3_4") (pintype "input"))
    )
    (net (code "17") (name "/AFSK1_RXD") (class "Default")
      (node (ref "U7") (pin "2") (pinfunction "A1_2") (pintype "input"))
    )
    (net (code "18") (name "/AFSK1_TXD") (class "Default")
      (node (ref "U7") (pin "5") (pinfunction "A4_5") (pintype "input"))
    )
    (net (code "19") (name "/AFSK2_DET") (class "Default")
      (node (ref "U14") (pin "3") (pinfunction "A2_3") (pintype "input"))
    )
    (net (code "20") (name "/AFSK2_M0") (class "Default")
      (node (ref "U7") (pin "8") (pinfunction "A7_8") (pintype "input"))
    )
    (net (code "21") (name "/AFSK2_M1") (class "Default")
      (node (ref "U7") (pin "9") (pinfunction "A8_9") (pintype "input"))
    )
    (net (code "22") (name "/AFSK2_RXD") (class "Default")
      (node (ref "U7") (pin "7") (pinfunction "A6_7") (pintype "input"))
    )
    (net (code "23") (name "/AFSK2_TXD") (class "Default")
      (node (ref "U14") (pin "2") (pinfunction "A1_2") (pintype "input"))
    )
    (net (code "24") (name "/BBONE_I2C2_SCL") (class "Default")
      (node (ref "U15") (pin "7") (pinfunction "A6_7") (pintype "input"))
    )
    (net (code "25") (name "/BBONE_I2C2_SDA") (class "Default")
      (node (ref "U15") (pin "6") (pinfunction "A5_6") (pintype "input"))
    )
    (net (code "26") (name "/BB_DEBUG_0") (class "Default")
      (node (ref "U16") (pin "2") (pinfunction "A1_2") (pintype "input"))
    )
    (net (code "27") (name "/BB_DEBUG_1") (class "Default")
      (node (ref "U16") (pin "3") (pinfunction "A2_3") (pintype "input"))
    )
    (net (code "28") (name "/BB_DEBUG_2") (class "Default")
      (node (ref "U16") (pin "4") (pinfunction "A3_4") (pintype "input"))
    )
    (net (code "29") (name "/BB_DEBUG_3") (class "Default")
      (node (ref "U16") (pin "5") (pinfunction "A4_5") (pintype "input"))
    )
    (net (code "30") (name "/BB_DEBUG_4") (class "Default")
      (node (ref "U16") (pin "6") (pinfunction "A5_6") (pintype "input"))
    )
    (net (code "31") (name "/BB_DEBUG_5") (class "Default")
      (node (ref "U16") (pin "7") (pinfunction "A6_7") (pintype "input"))
    )
    (net (code "32") (name "/BB_DEBUG_6") (class "Default")
      (node (ref "U16") (pin "8") (pinfunction "A7_8") (pintype "input"))
    )
    (net (code "33") (name "/BB_DEBUG_7") (class "Default")
      (node (ref "U16") (pin "9") (pinfunction "A8_9") (pintype "input"))
    )
    (net (code "34") (name "/BB_DEBUG_8") (class "Default")
      (node (ref "U17") (pin "2") (pinfunction "A1_2") (pintype "input"))
    )
    (net (code "35") (name "/BB_DEBUG_9") (class "Default")
      (node (ref "U17") (pin "3") (pinfunction "A2_3") (pintype "input"))
    )
    (net (code "36") (name "/BB_DEBUG_10") (class "Default")
      (node (ref "U17") (pin "4") (pinfunction "A3_4") (pintype "input"))
    )
    (net (code "37") (name "/BB_DEBUG_11") (class "Default")
      (node (ref "U17") (pin "5") (pinfunction "A4_5") (pintype "input"))
    )
    (net (code "38") (name "/BB_DEBUG_12") (class "Default")
      (node (ref "U17") (pin "6") (pinfunction "A5_6") (pintype "input"))
    )
    (net (code "39") (name "/BB_DEBUG_13") (class "Default")
      (node (ref "U17") (pin "7") (pinfunction "A6_7") (pintype "input"))
    )
    (net (code "40") (name "/BB_DEBUG_14") (class "Default")
      (node (ref "U17") (pin "8") (pinfunction "A7_8") (pintype "input"))
    )
    (net (code "41") (name "/DEBUG_0") (class "Default")
      (node (ref "U3") (pin "9") (pinfunction "A8_9") (pintype "input"))
    )
    (net (code "42") (name "/DEBUG_1") (class "Default")
      (node (ref "U3") (pin "8") (pinfunction "A7_8") (pintype "input"))
    )
    (net (code "43") (name "/DEBUG_2") (class "Default")
      (node (ref "U3") (pin "7") (pinfunction "A6_7") (pintype "input"))
    )
    (net (code "44") (name "/DEBUG_3") (class "Default")
      (node (ref "U3") (pin "6") (pinfunction "A5_6") (pintype "input"))
    )
    (net (code "45") (name "/DEBUG_4") (class "Default")
      (node (ref "U3") (pin "5") (pinfunction "A4_5") (pintype "input"))
    )
    (net (code "46") (name "/DEBUG_5") (class "Default")
      (node (ref "U3") (pin "4") (pinfunction "A3_4") (pintype "input"))
    )
    (net (code "47") (name "/DEBUG_6") (class "Default")
      (node (ref "U3") (pin "3") (pinfunction "A2_3") (pintype "input"))
    )
    (net (code "48") (name "/DEBUG_7") (class "Default")
      (node (ref "U3") (pin "2") (pinfunction "A1_2") (pintype "input"))
    )
    (net (code "49") (name "/DEBUG_8") (class "Default")
      (node (ref "U2") (pin "9") (pinfunction "A8_9") (pintype "input"))
    )
    (net (code "50") (name "/DEBUG_9") (class "Default")
      (node (ref "U2") (pin "8") (pinfunction "A7_8") (pintype "input"))
    )
    (net (code "51") (name "/DEBUG_10") (class "Default")
      (node (ref "U2") (pin "7") (pinfunction "A6_7") (pintype "input"))
    )
    (net (code "52") (name "/DEBUG_11") (class "Default")
      (node (ref "U2") (pin "6") (pinfunction "A5_6") (pintype "input"))
    )
    (net (code "53") (name "/DEBUG_12") (class "Default")
      (node (ref "U2") (pin "5") (pinfunction "A4_5") (pintype "input"))
    )
    (net (code "54") (name "/DEBUG_13") (class "Default")
      (node (ref "U2") (pin "4") (pinfunction "A3_4") (pintype "input"))
    )
    (net (code "55") (name "/DEBUG_14") (class "Default")
      (node (ref "U2") (pin "3") (pinfunction "A2_3") (pintype "input"))
    )
    (net (code "56") (name "/DEBUG_15") (class "Default")
      (node (ref "U2") (pin "2") (pinfunction "A1_2") (pintype "input"))
    )
    (net (code "57") (name "/DTMF1Q1") (class "Default")
      (node (ref "U4") (pin "2") (pinfunction "A1_2") (pintype "input"))
    )
    (net (code "58") (name "/DTMF1Q2") (class "Default")
      (node (ref "U4") (pin "3") (pinfunction "A2_3") (pintype "input"))
    )
    (net (code "59") (name "/DTMF1Q3") (class "Default")
      (node (ref "U4") (pin "4") (pinfunction "A3_4") (pintype "input"))
    )
    (net (code "60") (name "/DTMF1Q4") (class "Default")
      (node (ref "U4") (pin "5") (pinfunction "A4_5") (pintype "input"))
    )
    (net (code "61") (name "/DTMF1ST") (class "Default")
      (node (ref "U4") (pin "6") (pinfunction "A5_6") (pintype "input"))
    )
    (net (code "62") (name "/DTMF2Q1") (class "Default")
      (node (ref "U4") (pin "7") (pinfunction "A6_7") (pintype "input"))
    )
    (net (code "63") (name "/DTMF2Q2") (class "Default")
      (node (ref "U4") (pin "8") (pinfunction "A7_8") (pintype "input"))
    )
    (net (code "64") (name "/DTMF2Q3") (class "Default")
      (node (ref "U4") (pin "9") (pinfunction "A8_9") (pintype "input"))
    )
    (net (code "65") (name "/DTMF2Q4") (class "Default")
      (node (ref "U5") (pin "2") (pinfunction "A1_2") (pintype "input"))
    )
    (net (code "66") (name "/DTMF2ST") (class "Default")
      (node (ref "U5") (pin "3") (pinfunction "A2_3") (pintype "input"))
    )
    (net (code "67") (name "/I2C0_SCL") (class "Default")
      (node (ref "U5") (pin "5") (pinfunction "A4_5") (pintype "input"))
    )
    (net (code "68") (name "/I2C0_SDA") (class "Default")
      (node (ref "U5") (pin "4") (pinfunction "A3_4") (pintype "input"))
    )
    (net (code "69") (name "/I2C1_SCL") (class "Default")
      (node (ref "U5") (pin "7") (pinfunction "A6_7") (pintype "input"))
    )
    (net (code "70") (name "/I2C1_SDA") (class "Default")
      (node (ref "U5") (pin "6") (pinfunction "A5_6") (pintype "input"))
    )
    (net (code "71") (name "/I2C2_SCL") (class "Default")
      (node (ref "U5") (pin "9") (pinfunction "A8_9") (pintype "input"))
    )
    (net (code "72") (name "/I2C2_SDA") (class "Default")
      (node (ref "U5") (pin "8") (pinfunction "A7_8") (pintype "input"))
    )
    (net (code "73") (name "/RXDATA1") (class "Default")
      (node (ref "U14") (pin "5") (pinfunction "A4_5") (pintype "input"))
    )
    (net (code "74") (name "/RXDATA2") (class "Default")
      (node (ref "U15") (pin "2") (pinfunction "A1_2") (pintype "input"))
    )
    (net (code "75") (name "/RXHOLD1") (class "Default")
      (node (ref "U14") (pin "8") (pinfunction "A7_8") (pintype "input"))
    )
    (net (code "76") (name "/RXHOLD2") (class "Default")
      (node (ref "U15") (pin "5") (pinfunction "A4_5") (pintype "input"))
    )
    (net (code "77") (name "/RX_S{slash}N1") (class "Default")
      (node (ref "U14") (pin "7") (pinfunction "A6_7") (pintype "input"))
    )
    (net (code "78") (name "/RX_S{slash}N2") (class "Default")
      (node (ref "U15") (pin "4") (pinfunction "A3_4") (pintype "input"))
    )
    (net (code "79") (name "/S0") (class "Default")
      (node (ref "U6") (pin "2") (pinfunction "A1_2") (pintype "input"))
    )
    (net (code "80") (name "/S1") (class "Default")
      (node (ref "U6") (pin "3") (pinfunction "A2_3") (pintype "input"))
    )
    (net (code "81") (name "/S2") (class "Default")
      (node (ref "U6") (pin "4") (pinfunction "A3_4") (pintype "input"))
    )
    (net (code "82") (name "/S3") (class "Default")
      (node (ref "U6") (pin "5") (pinfunction "A4_5") (pintype "input"))
    )
    (net (code "83") (name "/S4") (class "Default")
      (node (ref "U6") (pin "6") (pinfunction "A5_6") (pintype "input"))
    )
    (net (code "84") (name "/S5") (class "Default")
      (node (ref "U6") (pin "7") (pinfunction "A6_7") (pintype "input"))
    )
    (net (code "85") (name "/S6") (class "Default")
      (node (ref "U6") (pin "8") (pinfunction "A7_8") (pintype "input"))
    )
    (net (code "86") (name "/S7") (class "Default")
      (node (ref "U6") (pin "9") (pinfunction "A8_9") (pintype "input"))
    )
    (net (code "87") (name "/TXDATA1") (class "Default")
      (node (ref "U14") (pin "4") (pinfunction "A3_4") (pintype "input"))
    )
    (net (code "88") (name "/TXDATA2") (class "Default")
      (node (ref "U14") (pin "9") (pinfunction "A8_9") (pintype "input"))
    )
    (net (code "89") (name "/TXEN1") (class "Default")
      (node (ref "U14") (pin "6") (pinfunction "A5_6") (pintype "input"))
    )
    (net (code "90") (name "/TXEN2") (class "Default")
      (node (ref "U15") (pin "3") (pinfunction "A2_3") (pintype "input"))
    )
    (net (code "91") (name "/VVAR_TX1") (class "Default")
      (node (ref "R25") (pin "2") (pinfunction "2_2") (pintype "passive"))
    )
    (net (code "92") (name "/VVAR_TX2") (class "Default")
      (node (ref "R27") (pin "2") (pinfunction "2_2") (pintype "passive"))
    )
    (net (code "93") (name "/V_BATT") (class "Default")
      (node (ref "R12") (pin "2") (pinfunction "2_2") (pintype "passive"))
    )
    (net (code "94") (name "/V_LOAD") (class "Default")
      (node (ref "R13") (pin "2") (pinfunction "2_2") (pintype "passive"))
    )
    (net (code "95") (name "3V3_UNREG") (class "Default")
      (node (ref "C10") (pin "2") (pinfunction "2_2") (pintype "passive"))
      (node (ref "C11") (pin "2") (pinfunction "2_2") (pintype "passive"))
      (node (ref "C12") (pin "2") (pinfunction "2_2") (pintype "passive"))
      (node (ref "C13") (pin "2") (pinfunction "2_2") (pintype "passive"))
      (node (ref "C2") (pin "2") (pinfunction "2_2") (pintype "passive"))
      (node (ref "C3") (pin "2") (pinfunction "2_2") (pintype "passive"))
      (node (ref "C4") (pin "2") (pinfunction "2_2") (pintype "passive"))
      (node (ref "C5") (pin "2") (pinfunction "2_2") (pintype "passive"))
      (node (ref "C6") (pin "2") (pinfunction "2_2") (pintype "passive"))
      (node (ref "C7") (pin "2") (pinfunction "2_2") (pintype "passive"))
      (node (ref "C8") (pin "2") (pinfunction "2_2") (pintype "passive"))
      (node (ref "C9") (pin "2") (pinfunction "2_2") (pintype "passive"))
      (node (ref "LED10") (pin "3") (pinfunction "VCC_3") (pintype "passive"))
      (node (ref "LED101") (pin "3") (pinfunction "VCC_3") (pintype "passive"))
      (node (ref "LED102") (pin "3") (pinfunction "VCC_3") (pintype "passive"))
      (node (ref "LED103") (pin "3") (pinfunction "VCC_3") (pintype "passive"))
      (node (ref "LED104") (pin "3") (pinfunction "VCC_3") (pintype "passive"))
      (node (ref "LED105") (pin "3") (pinfunction "VCC_3") (pintype "passive"))
      (node (ref "LED106") (pin "3") (pinfunction "VCC_3") (pintype "passive"))
      (node (ref "LED107") (pin "3") (pinfunction "VCC_3") (pintype "passive"))
      (node (ref "LED108") (pin "3") (pinfunction "VCC_3") (pintype "passive"))
      (node (ref "LED109") (pin "3") (pinfunction "VCC_3") (pintype "passive"))
      (node (ref "LED11") (pin "3") (pinfunction "VCC_3") (pintype "passive"))
      (node (ref "LED111") (pin "3") (pinfunction "VCC_3") (pintype "passive"))
      (node (ref "LED112") (pin "3") (pinfunction "VCC_3") (pintype "passive"))
      (node (ref "LED12") (pin "3") (pinfunction "VCC_3") (pintype "passive"))
      (node (ref "LED13") (pin "3") (pinfunction "VCC_3") (pintype "passive"))
      (node (ref "LED14") (pin "3") (pinfunction "VCC_3") (pintype "passive"))
      (node (ref "LED15") (pin "3") (pinfunction "VCC_3") (pintype "passive"))
      (node (ref "LED16") (pin "3") (pinfunction "VCC_3") (pintype "passive"))
      (node (ref "LED17") (pin "3") (pinfunction "VCC_3") (pintype "passive"))
      (node (ref "LED19") (pin "3") (pinfunction "VCC_3") (pintype "passive"))
      (node (ref "LED20") (pin "3") (pinfunction "VCC_3") (pintype "passive"))
      (node (ref "LED21") (pin "3") (pinfunction "VCC_3") (pintype "passive"))
      (node (ref "LED22") (pin "3") (pinfunction "VCC_3") (pintype "passive"))
      (node (ref "LED23") (pin "3") (pinfunction "VCC_3") (pintype "passive"))
      (node (ref "LED24") (pin "3") (pinfunction "VCC_3") (pintype "passive"))
      (node (ref "LED25") (pin "3") (pinfunction "VCC_3") (pintype "passive"))
      (node (ref "LED26") (pin "3") (pinfunction "VCC_3") (pintype "passive"))
      (node (ref "LED27") (pin "3") (pinfunction "VCC_3") (pintype "passive"))
      (node (ref "LED28") (pin "3") (pinfunction "VCC_3") (pintype "passive"))
      (node (ref "LED29") (pin "3") (pinfunction "VCC_3") (pintype "passive"))
      (node (ref "LED30") (pin "3") (pinfunction "VCC_3") (pintype "passive"))
      (node (ref "LED31") (pin "3") (pinfunction "VCC_3") (pintype "passive"))
      (node (ref "LED32") (pin "3") (pinfunction "VCC_3") (pintype "passive"))
      (node (ref "LED33") (pin "3") (pinfunction "VCC_3") (pintype "passive"))
      (node (ref "LED34") (pin "3") (pinfunction "VCC_3") (pintype "passive"))
      (node (ref "LED35") (pin "3") (pinfunction "VCC_3") (pintype "passive"))
      (node (ref "LED36") (pin "3") (pinfunction "VCC_3") (pintype "passive"))
      (node (ref "LED38") (pin "3") (pinfunction "VCC_3") (pintype "passive"))
      (node (ref "LED39") (pin "3") (pinfunction "VCC_3") (pintype "passive"))
      (node (ref "LED40") (pin "3") (pinfunction "VCC_3") (pintype "passive"))
      (node (ref "LED41") (pin "3") (pinfunction "VCC_3") (pintype "passive"))
      (node (ref "LED42") (pin "3") (pinfunction "VCC_3") (pintype "passive"))
      (node (ref "LED43") (pin "3") (pinfunction "VCC_3") (pintype "passive"))
      (node (ref "LED44") (pin "3") (pinfunction "VCC_3") (pintype "passive"))
      (node (ref "LED45") (pin "3") (pinfunction "VCC_3") (pintype "passive"))
      (node (ref "LED46") (pin "3") (pinfunction "VCC_3") (pintype "passive"))
      (node (ref "LED47") (pin "3") (pinfunction "VCC_3") (pintype "passive"))
      (node (ref "LED48") (pin "3") (pinfunction "VCC_3") (pintype "passive"))
      (node (ref "LED49") (pin "3") (pinfunction "VCC_3") (pintype "passive"))
      (node (ref "LED50") (pin "3") (pinfunction "VCC_3") (pintype "passive"))
      (node (ref "LED51") (pin "3") (pinfunction "VCC_3") (pintype "passive"))
      (node (ref "LED52") (pin "3") (pinfunction "VCC_3") (pintype "passive"))
      (node (ref "LED53") (pin "3") (pinfunction "VCC_3") (pintype "passive"))
      (node (ref "LED54") (pin "3") (pinfunction "VCC_3") (pintype "passive"))
      (node (ref "LED55") (pin "3") (pinfunction "VCC_3") (pintype "passive"))
      (node (ref "LED6") (pin "3") (pinfunction "VCC_3") (pintype "passive"))
      (node (ref "LED63") (pin "3") (pinfunction "VCC_3") (pintype "passive"))
      (node (ref "LED64") (pin "3") (pinfunction "VCC_3") (pintype "passive"))
      (node (ref "LED65") (pin "3") (pinfunction "VCC_3") (pintype "passive"))
      (node (ref "LED66") (pin "3") (pinfunction "VCC_3") (pintype "passive"))
      (node (ref "LED67") (pin "3") (pinfunction "VCC_3") (pintype "passive"))
      (node (ref "LED68") (pin "3") (pinfunction "VCC_3") (pintype "passive"))
      (node (ref "LED69") (pin "3") (pinfunction "VCC_3") (pintype "passive"))
      (node (ref "LED7") (pin "3") (pinfunction "VCC_3") (pintype "passive"))
      (node (ref "LED70") (pin "3") (pinfunction "VCC_3") (pintype "passive"))
      (node (ref "LED71") (pin "3") (pinfunction "VCC_3") (pintype "passive"))
      (node (ref "LED72") (pin "3") (pinfunction "VCC_3") (pintype "passive"))
      (node (ref "LED73") (pin "3") (pinfunction "VCC_3") (pintype "passive"))
      (node (ref "LED74") (pin "3") (pinfunction "VCC_3") (pintype "passive"))
      (node (ref "LED75") (pin "3") (pinfunction "VCC_3") (pintype "passive"))
      (node (ref "LED76") (pin "3") (pinfunction "VCC_3") (pintype "passive"))
      (node (ref "LED77") (pin "3") (pinfunction "VCC_3") (pintype "passive"))
      (node (ref "LED78") (pin "3") (pinfunction "VCC_3") (pintype "passive"))
      (node (ref "LED79") (pin "3") (pinfunction "VCC_3") (pintype "passive"))
      (node (ref "LED8") (pin "3") (pinfunction "VCC_3") (pintype "passive"))
      (node (ref "LED80") (pin "3") (pinfunction "VCC_3") (pintype "passive"))
      (node (ref "LED82") (pin "3") (pinfunction "VCC_3") (pintype "passive"))
      (node (ref "LED83") (pin "3") (pinfunction "VCC_3") (pintype "passive"))
      (node (ref "LED84") (pin "3") (pinfunction "VCC_3") (pintype "passive"))
      (node (ref "LED85") (pin "3") (pinfunction "VCC_3") (pintype "passive"))
      (node (ref "LED86") (pin "3") (pinfunction "VCC_3") (pintype "passive"))
      (node (ref "LED87") (pin "3") (pinfunction "VCC_3") (pintype "passive"))
      (node (ref "LED88") (pin "3") (pinfunction "VCC_3") (pintype "passive"))
      (node (ref "LED89") (pin "3") (pinfunction "VCC_3") (pintype "passive"))
      (node (ref "LED9") (pin "3") (pinfunction "VCC_3") (pintype "passive"))
      (node (ref "LED90") (pin "3") (pinfunction "VCC_3") (pintype "passive"))
      (node (ref "LED91") (pin "3") (pinfunction "VCC_3") (pintype "passive"))
      (node (ref "LED92") (pin "3") (pinfunction "VCC_3") (pintype "passive"))
      (node (ref "LED93") (pin "3") (pinfunction "VCC_3") (pintype "passive"))
      (node (ref "LED94") (pin "3") (pinfunction "VCC_3") (pintype "passive"))
      (node (ref "LED95") (pin "3") (pinfunction "VCC_3") (pintype "passive"))
      (node (ref "LED96") (pin "3") (pinfunction "VCC_3") (pintype "passive"))
      (node (ref "LED97") (pin "3") (pinfunction "VCC_3") (pintype "passive"))
      (node (ref "LED98") (pin "3") (pinfunction "VCC_3") (pintype "passive"))
      (node (ref "LED99") (pin "3") (pinfunction "VCC_3") (pintype "passive"))
      (node (ref "R14") (pin "2") (pinfunction "2_2") (pintype "passive"))
      (node (ref "U14") (pin "20") (pinfunction "VDD_20") (pintype "power_in"))
      (node (ref "U15") (pin "20") (pinfunction "VDD_20") (pintype "power_in"))
      (node (ref "U16") (pin "20") (pinfunction "VDD_20") (pintype "power_in"))
      (node (ref "U17") (pin "20") (pinfunction "VDD_20") (pintype "power_in"))
      (node (ref "U18") (pin "20") (pinfunction "VDD_20") (pintype "power_in"))
      (node (ref "U19") (pin "20") (pinfunction "VDD_20") (pintype "power_in"))
      (node (ref "U2") (pin "20") (pinfunction "VDD_20") (pintype "power_in"))
      (node (ref "U3") (pin "20") (pinfunction "VDD_20") (pintype "power_in"))
      (node (ref "U4") (pin "20") (pinfunction "VDD_20") (pintype "power_in"))
      (node (ref "U5") (pin "20") (pinfunction "VDD_20") (pintype "power_in"))
      (node (ref "U6") (pin "20") (pinfunction "VDD_20") (pintype "power_in"))
      (node (ref "U7") (pin "20") (pinfunction "VDD_20") (pintype "power_in"))
    )
    (net (code "96") (name "GND") (class "Default")
      (node (ref "C10") (pin "1") (pinfunction "1_1") (pintype "passive"))
      (node (ref "C11") (pin "1") (pinfunction "1_1") (pintype "passive"))
      (node (ref "C12") (pin "1") (pinfunction "1_1") (pintype "passive"))
      (node (ref "C13") (pin "1") (pinfunction "1_1") (pintype "passive"))
      (node (ref "C2") (pin "1") (pinfunction "1_1") (pintype "passive"))
      (node (ref "C3") (pin "1") (pinfunction "1_1") (pintype "passive"))
      (node (ref "C4") (pin "1") (pinfunction "1_1") (pintype "passive"))
      (node (ref "C5") (pin "1") (pinfunction "1_1") (pintype "passive"))
      (node (ref "C6") (pin "1") (pinfunction "1_1") (pintype "passive"))
      (node (ref "C7") (pin "1") (pinfunction "1_1") (pintype "passive"))
      (node (ref "C8") (pin "1") (pinfunction "1_1") (pintype "passive"))
      (node (ref "C9") (pin "1") (pinfunction "1_1") (pintype "passive"))
      (node (ref "LED1") (pin "2") (pinfunction "K_2") (pintype "passive"))
      (node (ref "LED10") (pin "1") (pinfunction "GND_1") (pintype "passive"))
      (node (ref "LED100") (pin "2") (pinfunction "K_2") (pintype "passive"))
      (node (ref "LED101") (pin "1") (pinfunction "GND_1") (pintype "passive"))
      (node (ref "LED102") (pin "1") (pinfunction "GND_1") (pintype "passive"))
      (node (ref "LED103") (pin "1") (pinfunction "GND_1") (pintype "passive"))
      (node (ref "LED104") (pin "1") (pinfunction "GND_1") (pintype "passive"))
      (node (ref "LED105") (pin "1") (pinfunction "GND_1") (pintype "passive"))
      (node (ref "LED106") (pin "1") (pinfunction "GND_1") (pintype "passive"))
      (node (ref "LED107") (pin "1") (pinfunction "GND_1") (pintype "passive"))
      (node (ref "LED108") (pin "1") (pinfunction "GND_1") (pintype "passive"))
      (node (ref "LED109") (pin "1") (pinfunction "GND_1") (pintype "passive"))
      (node (ref "LED11") (pin "1") (pinfunction "GND_1") (pintype "passive"))
      (node (ref "LED111") (pin "1") (pinfunction "GND_1") (pintype "passive"))
      (node (ref "LED112") (pin "1") (pinfunction "GND_1") (pintype "passive"))
      (node (ref "LED12") (pin "1") (pinfunction "GND_1") (pintype "passive"))
      (node (ref "LED13") (pin "1") (pinfunction "GND_1") (pintype "passive"))
      (node (ref "LED14") (pin "1") (pinfunction "GND_1") (pintype "passive"))
      (node (ref "LED15") (pin "1") (pinfunction "GND_1") (pintype "passive"))
      (node (ref "LED16") (pin "1") (pinfunction "GND_1") (pintype "passive"))
      (node (ref "LED17") (pin "1") (pinfunction "GND_1") (pintype "passive"))
      (node (ref "LED18") (pin "2") (pinfunction "K_2") (pintype "passive"))
      (node (ref "LED19") (pin "1") (pinfunction "GND_1") (pintype "passive"))
      (node (ref "LED2") (pin "2") (pinfunction "K_2") (pintype "passive"))
      (node (ref "LED20") (pin "1") (pinfunction "GND_1") (pintype "passive"))
      (node (ref "LED21") (pin "1") (pinfunction "GND_1") (pintype "passive"))
      (node (ref "LED22") (pin "1") (pinfunction "GND_1") (pintype "passive"))
      (node (ref "LED23") (pin "1") (pinfunction "GND_1") (pintype "passive"))
      (node (ref "LED24") (pin "1") (pinfunction "GND_1") (pintype "passive"))
      (node (ref "LED25") (pin "1") (pinfunction "GND_1") (pintype "passive"))
      (node (ref "LED26") (pin "1") (pinfunction "GND_1") (pintype "passive"))
      (node (ref "LED27") (pin "1") (pinfunction "GND_1") (pintype "passive"))
      (node (ref "LED28") (pin "1") (pinfunction "GND_1") (pintype "passive"))
      (node (ref "LED29") (pin "1") (pinfunction "GND_1") (pintype "passive"))
      (node (ref "LED3") (pin "2") (pinfunction "K_2") (pintype "passive"))
      (node (ref "LED30") (pin "1") (pinfunction "GND_1") (pintype "passive"))
      (node (ref "LED31") (pin "1") (pinfunction "GND_1") (pintype "passive"))
      (node (ref "LED32") (pin "1") (pinfunction "GND_1") (pintype "passive"))
      (node (ref "LED33") (pin "1") (pinfunction "GND_1") (pintype "passive"))
      (node (ref "LED34") (pin "1") (pinfunction "GND_1") (pintype "passive"))
      (node (ref "LED35") (pin "1") (pinfunction "GND_1") (pintype "passive"))
      (node (ref "LED36") (pin "1") (pinfunction "GND_1") (pintype "passive"))
      (node (ref "LED37") (pin "2") (pinfunction "K_2") (pintype "passive"))
      (node (ref "LED38") (pin "1") (pinfunction "GND_1") (pintype "passive"))
      (node (ref "LED39") (pin "1") (pinfunction "GND_1") (pintype "passive"))
      (node (ref "LED4") (pin "2") (pinfunction "K_2") (pintype "passive"))
      (node (ref "LED40") (pin "1") (pinfunction "GND_1") (pintype "passive"))
      (node (ref "LED41") (pin "1") (pinfunction "GND_1") (pintype "passive"))
      (node (ref "LED42") (pin "1") (pinfunction "GND_1") (pintype "passive"))
      (node (ref "LED43") (pin "1") (pinfunction "GND_1") (pintype "passive"))
      (node (ref "LED44") (pin "1") (pinfunction "GND_1") (pintype "passive"))
      (node (ref "LED45") (pin "1") (pinfunction "GND_1") (pintype "passive"))
      (node (ref "LED46") (pin "1") (pinfunction "GND_1") (pintype "passive"))
      (node (ref "LED47") (pin "1") (pinfunction "GND_1") (pintype "passive"))
      (node (ref "LED48") (pin "1") (pinfunction "GND_1") (pintype "passive"))
      (node (ref "LED49") (pin "1") (pinfunction "GND_1") (pintype "passive"))
      (node (ref "LED5") (pin "2") (pinfunction "K_2") (pintype "passive"))
      (node (ref "LED50") (pin "1") (pinfunction "GND_1") (pintype "passive"))
      (node (ref "LED51") (pin "1") (pinfunction "GND_1") (pintype "passive"))
      (node (ref "LED52") (pin "1") (pinfunction "GND_1") (pintype "passive"))
      (node (ref "LED53") (pin "1") (pinfunction "GND_1") (pintype "passive"))
      (node (ref "LED54") (pin "1") (pinfunction "GND_1") (pintype "passive"))
      (node (ref "LED55") (pin "1") (pinfunction "GND_1") (pintype "passive"))
      (node (ref "LED56") (pin "2") (pinfunction "K_2") (pintype "passive"))
      (node (ref "LED57") (pin "2") (pinfunction "K_2") (pintype "passive"))
      (node (ref "LED58") (pin "2") (pinfunction "K_2") (pintype "passive"))
      (node (ref "LED59") (pin "2") (pinfunction "K_2") (pintype "passive"))
      (node (ref "LED6") (pin "1") (pinfunction "GND_1") (pintype "passive"))
      (node (ref "LED60") (pin "2") (pinfunction "K_2") (pintype "passive"))
      (node (ref "LED61") (pin "2") (pinfunction "K_2") (pintype "passive"))
      (node (ref "LED62") (pin "2") (pinfunction "K_2") (pintype "passive"))
      (node (ref "LED63") (pin "1") (pinfunction "GND_1") (pintype "passive"))
      (node (ref "LED64") (pin "1") (pinfunction "GND_1") (pintype "passive"))
      (node (ref "LED65") (pin "1") (pinfunction "GND_1") (pintype "passive"))
      (node (ref "LED66") (pin "1") (pinfunction "GND_1") (pintype "passive"))
      (node (ref "LED67") (pin "1") (pinfunction "GND_1") (pintype "passive"))
      (node (ref "LED68") (pin "1") (pinfunction "GND_1") (pintype "passive"))
      (node (ref "LED69") (pin "1") (pinfunction "GND_1") (pintype "passive"))
      (node (ref "LED7") (pin "1") (pinfunction "GND_1") (pintype "passive"))
      (node (ref "LED70") (pin "1") (pinfunction "GND_1") (pintype "passive"))
      (node (ref "LED71") (pin "1") (pinfunction "GND_1") (pintype "passive"))
      (node (ref "LED72") (pin "1") (pinfunction "GND_1") (pintype "passive"))
      (node (ref "LED73") (pin "1") (pinfunction "GND_1") (pintype "passive"))
      (node (ref "LED74") (pin "1") (pinfunction "GND_1") (pintype "passive"))
      (node (ref "LED75") (pin "1") (pinfunction "GND_1") (pintype "passive"))
      (node (ref "LED76") (pin "1") (pinfunction "GND_1") (pintype "passive"))
      (node (ref "LED77") (pin "1") (pinfunction "GND_1") (pintype "passive"))
      (node (ref "LED78") (pin "1") (pinfunction "GND_1") (pintype "passive"))
      (node (ref "LED79") (pin "1") (pinfunction "GND_1") (pintype "passive"))
      (node (ref "LED8") (pin "1") (pinfunction "GND_1") (pintype "passive"))
      (node (ref "LED80") (pin "1") (pinfunction "GND_1") (pintype "passive"))
      (node (ref "LED81") (pin "2") (pinfunction "K_2") (pintype "passive"))
      (node (ref "LED82") (pin "1") (pinfunction "GND_1") (pintype "passive"))
      (node (ref "LED83") (pin "1") (pinfunction "GND_1") (pintype "passive"))
      (node (ref "LED84") (pin "1") (pinfunction "GND_1") (pintype "passive"))
      (node (ref "LED85") (pin "1") (pinfunction "GND_1") (pintype "passive"))
      (node (ref "LED86") (pin "1") (pinfunction "GND_1") (pintype "passive"))
      (node (ref "LED87") (pin "1") (pinfunction "GND_1") (pintype "passive"))
      (node (ref "LED88") (pin "1") (pinfunction "GND_1") (pintype "passive"))
      (node (ref "LED89") (pin "1") (pinfunction "GND_1") (pintype "passive"))
      (node (ref "LED9") (pin "1") (pinfunction "GND_1") (pintype "passive"))
      (node (ref "LED90") (pin "1") (pinfunction "GND_1") (pintype "passive"))
      (node (ref "LED91") (pin "1") (pinfunction "GND_1") (pintype "passive"))
      (node (ref "LED92") (pin "1") (pinfunction "GND_1") (pintype "passive"))
      (node (ref "LED93") (pin "1") (pinfunction "GND_1") (pintype "passive"))
      (node (ref "LED94") (pin "1") (pinfunction "GND_1") (pintype "passive"))
      (node (ref "LED95") (pin "1") (pinfunction "GND_1") (pintype "passive"))
      (node (ref "LED96") (pin "1") (pinfunction "GND_1") (pintype "passive"))
      (node (ref "LED97") (pin "1") (pinfunction "GND_1") (pintype "passive"))
      (node (ref "LED98") (pin "1") (pinfunction "GND_1") (pintype "passive"))
      (node (ref "LED99") (pin "1") (pinfunction "GND_1") (pintype "passive"))
      (node (ref "U14") (pin "1") (pinfunction "~{OE}1_1") (pintype "input"))
      (node (ref "U14") (pin "10") (pinfunction "GND_10") (pintype "power_in"))
      (node (ref "U14") (pin "19") (pinfunction "~{OE}2_19") (pintype "input"))
      (node (ref "U15") (pin "1") (pinfunction "~{OE}1_1") (pintype "input"))
      (node (ref "U15") (pin "10") (pinfunction "GND_10") (pintype "power_in"))
      (node (ref "U15") (pin "19") (pinfunction "~{OE}2_19") (pintype "input"))
      (node (ref "U16") (pin "1") (pinfunction "~{OE}1_1") (pintype "input"))
      (node (ref "U16") (pin "10") (pinfunction "GND_10") (pintype "power_in"))
      (node (ref "U16") (pin "19") (pinfunction "~{OE}2_19") (pintype "input"))
      (node (ref "U17") (pin "1") (pinfunction "~{OE}1_1") (pintype "input"))
      (node (ref "U17") (pin "10") (pinfunction "GND_10") (pintype "power_in"))
      (node (ref "U17") (pin "19") (pinfunction "~{OE}2_19") (pintype "input"))
      (node (ref "U18") (pin "1") (pinfunction "~{OE}1_1") (pintype "input"))
      (node (ref "U18") (pin "10") (pinfunction "GND_10") (pintype "power_in"))
      (node (ref "U18") (pin "19") (pinfunction "~{OE}2_19") (pintype "input"))
      (node (ref "U19") (pin "1") (pinfunction "~{OE}1_1") (pintype "input"))
      (node (ref "U19") (pin "19") (pinfunction "~{OE}2_19") (pintype "input"))
      (node (ref "U2") (pin "1") (pinfunction "~{OE}1_1") (pintype "input"))
      (node (ref "U2") (pin "10") (pinfunction "GND_10") (pintype "power_in"))
      (node (ref "U2") (pin "19") (pinfunction "~{OE}2_19") (pintype "input"))
      (node (ref "U3") (pin "1") (pinfunction "~{OE}1_1") (pintype "input"))
      (node (ref "U3") (pin "10") (pinfunction "GND_10") (pintype "power_in"))
      (node (ref "U3") (pin "19") (pinfunction "~{OE}2_19") (pintype "input"))
      (node (ref "U4") (pin "1") (pinfunction "~{OE}1_1") (pintype "input"))
      (node (ref "U4") (pin "10") (pinfunction "GND_10") (pintype "power_in"))
      (node (ref "U4") (pin "19") (pinfunction "~{OE}2_19") (pintype "input"))
      (node (ref "U5") (pin "1") (pinfunction "~{OE}1_1") (pintype "input"))
      (node (ref "U5") (pin "10") (pinfunction "GND_10") (pintype "power_in"))
      (node (ref "U5") (pin "19") (pinfunction "~{OE}2_19") (pintype "input"))
      (node (ref "U6") (pin "1") (pinfunction "~{OE}1_1") (pintype "input"))
      (node (ref "U6") (pin "10") (pinfunction "GND_10") (pintype "power_in"))
      (node (ref "U6") (pin "19") (pinfunction "~{OE}2_19") (pintype "input"))
      (node (ref "U7") (pin "1") (pinfunction "~{OE}1_1") (pintype "input"))
      (node (ref "U7") (pin "10") (pinfunction "GND_10") (pintype "power_in"))
      (node (ref "U7") (pin "19") (pinfunction "~{OE}2_19") (pintype "input"))
    )
    (net (code "97") (name "Net-(LED1-A)") (class "Default")
      (node (ref "LED1") (pin "1") (pinfunction "A_1") (pintype "passive"))
      (node (ref "R12") (pin "1") (pinfunction "1_1") (pintype "passive"))
    )
    (net (code "98") (name "Net-(LED2-A)") (class "Default")
      (node (ref "LED2") (pin "1") (pinfunction "A_1") (pintype "passive"))
      (node (ref "R13") (pin "1") (pinfunction "1_1") (pintype "passive"))
    )
    (net (code "99") (name "Net-(LED3-A)") (class "Default")
      (node (ref "LED3") (pin "1") (pinfunction "A_1") (pintype "passive"))
      (node (ref "R14") (pin "1") (pinfunction "1_1") (pintype "passive"))
    )
    (net (code "100") (name "Net-(LED4-A)") (class "Default")
      (node (ref "LED4") (pin "1") (pinfunction "A_1") (pintype "passive"))
      (node (ref "R15") (pin "1") (pinfunction "1_1") (pintype "passive"))
    )
    (net (code "101") (name "Net-(LED5-A)") (class "Default")
      (node (ref "LED5") (pin "1") (pinfunction "A_1") (pintype "passive"))
      (node (ref "R16") (pin "1") (pinfunction "1_1") (pintype "passive"))
    )
    (net (code "102") (name "Net-(LED6-RES)") (class "Default")
      (node (ref "LED6") (pin "2") (pinfunction "RES_2") (pintype "passive"))
      (node (ref "U8") (pin "16") (pinfunction "1B_16") (pintype "passive"))
    )
    (net (code "103") (name "Net-(LED7-RES)") (class "Default")
      (node (ref "LED7") (pin "2") (pinfunction "RES_2") (pintype "passive"))
      (node (ref "U9") (pin "16") (pinfunction "1B_16") (pintype "passive"))
    )
    (net (code "104") (name "Net-(LED8-RES)") (class "Default")
      (node (ref "LED8") (pin "2") (pinfunction "RES_2") (pintype "passive"))
      (node (ref "U10") (pin "16") (pinfunction "1B_16") (pintype "passive"))
    )
    (net (code "105") (name "Net-(LED9-RES)") (class "Default")
      (node (ref "LED9") (pin "2") (pinfunction "RES_2") (pintype "passive"))
      (node (ref "U11") (pin "16") (pinfunction "1B_16") (pintype "passive"))
    )
    (net (code "106") (name "Net-(LED10-RES)") (class "Default")
      (node (ref "LED10") (pin "2") (pinfunction "RES_2") (pintype "passive"))
      (node (ref "U12") (pin "16") (pinfunction "1B_16") (pintype "passive"))
    )
    (net (code "107") (name "Net-(LED11-RES)") (class "Default")
      (node (ref "LED11") (pin "2") (pinfunction "RES_2") (pintype "passive"))
      (node (ref "U13") (pin "16") (pinfunction "1B_16") (pintype "passive"))
    )
    (net (code "108") (name "Net-(LED12-RES)") (class "Default")
      (node (ref "LED12") (pin "2") (pinfunction "RES_2") (pintype "passive"))
      (node (ref "U8") (pin "15") (pinfunction "2B_15") (pintype "passive"))
    )
    (net (code "109") (name "Net-(LED13-RES)") (class "Default")
      (node (ref "LED13") (pin "2") (pinfunction "RES_2") (pintype "passive"))
      (node (ref "U9") (pin "15") (pinfunction "2B_15") (pintype "passive"))
    )
    (net (code "110") (name "Net-(LED14-RES)") (class "Default")
      (node (ref "LED14") (pin "2") (pinfunction "RES_2") (pintype "passive"))
      (node (ref "U10") (pin "15") (pinfunction "2B_15") (pintype "passive"))
    )
    (net (code "111") (name "Net-(LED15-RES)") (class "Default")
      (node (ref "LED15") (pin "2") (pinfunction "RES_2") (pintype "passive"))
      (node (ref "U11") (pin "15") (pinfunction "2B_15") (pintype "passive"))
    )
    (net (code "112") (name "Net-(LED16-RES)") (class "Default")
      (node (ref "LED16") (pin "2") (pinfunction "RES_2") (pintype "passive"))
      (node (ref "U12") (pin "15") (pinfunction "2B_15") (pintype "passive"))
    )
    (net (code "113") (name "Net-(LED17-RES)") (class "Default")
      (node (ref "LED17") (pin "2") (pinfunction "RES_2") (pintype "passive"))
      (node (ref "U13") (pin "15") (pinfunction "2B_15") (pintype "passive"))
    )
    (net (code "114") (name "Net-(LED18-A)") (class "Default")
      (node (ref "LED18") (pin "1") (pinfunction "A_1") (pintype "passive"))
      (node (ref "R17") (pin "1") (pinfunction "1_1") (pintype "passive"))
    )
    (net (code "115") (name "Net-(LED19-RES)") (class "Default")
      (node (ref "LED19") (pin "2") (pinfunction "RES_2") (pintype "passive"))
      (node (ref "U8") (pin "14") (pinfunction "3B_14") (pintype "passive"))
    )
    (net (code "116") (name "Net-(LED20-RES)") (class "Default")
      (node (ref "LED20") (pin "2") (pinfunction "RES_2") (pintype "passive"))
      (node (ref "U9") (pin "14") (pinfunction "3B_14") (pintype "passive"))
    )
    (net (code "117") (name "Net-(LED21-RES)") (class "Default")
      (node (ref "LED21") (pin "2") (pinfunction "RES_2") (pintype "passive"))
      (node (ref "U10") (pin "14") (pinfunction "3B_14") (pintype "passive"))
    )
    (net (code "118") (name "Net-(LED22-RES)") (class "Default")
      (node (ref "LED22") (pin "2") (pinfunction "RES_2") (pintype "passive"))
      (node (ref "U11") (pin "14") (pinfunction "3B_14") (pintype "passive"))
    )
    (net (code "119") (name "Net-(LED23-RES)") (class "Default")
      (node (ref "LED23") (pin "2") (pinfunction "RES_2") (pintype "passive"))
      (node (ref "U12") (pin "14") (pinfunction "3B_14") (pintype "passive"))
    )
    (net (code "120") (name "Net-(LED24-RES)") (class "Default")
      (node (ref "LED24") (pin "2") (pinfunction "RES_2") (pintype "passive"))
      (node (ref "U13") (pin "14") (pinfunction "3B_14") (pintype "passive"))
    )
    (net (code "121") (name "Net-(LED25-RES)") (class "Default")
      (node (ref "LED25") (pin "2") (pinfunction "RES_2") (pintype "passive"))
      (node (ref "U8") (pin "13") (pinfunction "4B_13") (pintype "passive"))
    )
    (net (code "122") (name "Net-(LED26-RES)") (class "Default")
      (node (ref "LED26") (pin "2") (pinfunction "RES_2") (pintype "passive"))
      (node (ref "U9") (pin "13") (pinfunction "4B_13") (pintype "passive"))
    )
    (net (code "123") (name "Net-(LED27-RES)") (class "Default")
      (node (ref "LED27") (pin "2") (pinfunction "RES_2") (pintype "passive"))
      (node (ref "U10") (pin "13") (pinfunction "4B_13") (pintype "passive"))
    )
    (net (code "124") (name "Net-(LED28-RES)") (class "Default")
      (node (ref "LED28") (pin "2") (pinfunction "RES_2") (pintype "passive"))
      (node (ref "U11") (pin "13") (pinfunction "4B_13") (pintype "passive"))
    )
    (net (code "125") (name "Net-(LED29-RES)") (class "Default")
      (node (ref "LED29") (pin "2") (pinfunction "RES_2") (pintype "passive"))
      (node (ref "U12") (pin "13") (pinfunction "4B_13") (pintype "passive"))
    )
    (net (code "126") (name "Net-(LED30-RES)") (class "Default")
      (node (ref "LED30") (pin "2") (pinfunction "RES_2") (pintype "passive"))
      (node (ref "U13") (pin "13") (pinfunction "4B_13") (pintype "passive"))
    )
    (net (code "127") (name "Net-(LED31-RES)") (class "Default")
      (node (ref "LED31") (pin "2") (pinfunction "RES_2") (pintype "passive"))
      (node (ref "U8") (pin "12") (pinfunction "5B_12") (pintype "passive"))
    )
    (net (code "128") (name "Net-(LED32-RES)") (class "Default")
      (node (ref "LED32") (pin "2") (pinfunction "RES_2") (pintype "passive"))
      (node (ref "U9") (pin "12") (pinfunction "5B_12") (pintype "passive"))
    )
    (net (code "129") (name "Net-(LED33-RES)") (class "Default")
      (node (ref "LED33") (pin "2") (pinfunction "RES_2") (pintype "passive"))
      (node (ref "U10") (pin "12") (pinfunction "5B_12") (pintype "passive"))
    )
    (net (code "130") (name "Net-(LED34-RES)") (class "Default")
      (node (ref "LED34") (pin "2") (pinfunction "RES_2") (pintype "passive"))
      (node (ref "U11") (pin "12") (pinfunction "5B_12") (pintype "passive"))
    )
    (net (code "131") (name "Net-(LED35-RES)") (class "Default")
      (node (ref "LED35") (pin "2") (pinfunction "RES_2") (pintype "passive"))
      (node (ref "U12") (pin "12") (pinfunction "5B_12") (pintype "passive"))
    )
    (net (code "132") (name "Net-(LED36-RES)") (class "Default")
      (node (ref "LED36") (pin "2") (pinfunction "RES_2") (pintype "passive"))
      (node (ref "U13") (pin "12") (pinfunction "5B_12") (pintype "passive"))
    )
    (net (code "133") (name "Net-(LED37-A)") (class "Default")
      (node (ref "LED37") (pin "1") (pinfunction "A_1") (pintype "passive"))
      (node (ref "R18") (pin "1") (pinfunction "1_1") (pintype "passive"))
    )
    (net (code "134") (name "Net-(LED38-RES)") (class "Default")
      (node (ref "LED38") (pin "2") (pinfunction "RES_2") (pintype "passive"))
      (node (ref "U8") (pin "11") (pinfunction "6B_11") (pintype "passive"))
    )
    (net (code "135") (name "Net-(LED39-RES)") (class "Default")
      (node (ref "LED39") (pin "2") (pinfunction "RES_2") (pintype "passive"))
      (node (ref "U9") (pin "11") (pinfunction "6B_11") (pintype "passive"))
    )
    (net (code "136") (name "Net-(LED40-RES)") (class "Default")
      (node (ref "LED40") (pin "2") (pinfunction "RES_2") (pintype "passive"))
      (node (ref "U10") (pin "11") (pinfunction "6B_11") (pintype "passive"))
    )
    (net (code "137") (name "Net-(LED41-RES)") (class "Default")
      (node (ref "LED41") (pin "2") (pinfunction "RES_2") (pintype "passive"))
      (node (ref "U11") (pin "11") (pinfunction "6B_11") (pintype "passive"))
    )
    (net (code "138") (name "Net-(LED42-RES)") (class "Default")
      (node (ref "LED42") (pin "2") (pinfunction "RES_2") (pintype "passive"))
      (node (ref "U12") (pin "11") (pinfunction "6B_11") (pintype "passive"))
    )
    (net (code "139") (name "Net-(LED43-RES)") (class "Default")
      (node (ref "LED43") (pin "2") (pinfunction "RES_2") (pintype "passive"))
      (node (ref "U13") (pin "11") (pinfunction "6B_11") (pintype "passive"))
    )
    (net (code "140") (name "Net-(LED44-RES)") (class "Default")
      (node (ref "LED44") (pin "2") (pinfunction "RES_2") (pintype "passive"))
      (node (ref "U8") (pin "10") (pinfunction "7B_10") (pintype "passive"))
    )
    (net (code "141") (name "Net-(LED45-RES)") (class "Default")
      (node (ref "LED45") (pin "2") (pinfunction "RES_2") (pintype "passive"))
      (node (ref "U9") (pin "10") (pinfunction "7B_10") (pintype "passive"))
    )
    (net (code "142") (name "Net-(LED46-RES)") (class "Default")
      (node (ref "LED46") (pin "2") (pinfunction "RES_2") (pintype "passive"))
      (node (ref "U10") (pin "10") (pinfunction "7B_10") (pintype "passive"))
    )
    (net (code "143") (name "Net-(LED47-RES)") (class "Default")
      (node (ref "LED47") (pin "2") (pinfunction "RES_2") (pintype "passive"))
      (node (ref "U11") (pin "10") (pinfunction "7B_10") (pintype "passive"))
    )
    (net (code "144") (name "Net-(LED48-RES)") (class "Default")
      (node (ref "LED48") (pin "2") (pinfunction "RES_2") (pintype "passive"))
      (node (ref "U12") (pin "10") (pinfunction "7B_10") (pintype "passive"))
    )
    (net (code "145") (name "Net-(LED49-RES)") (class "Default")
      (node (ref "LED49") (pin "2") (pinfunction "RES_2") (pintype "passive"))
      (node (ref "U13") (pin "10") (pinfunction "7B_10") (pintype "passive"))
    )
    (net (code "146") (name "Net-(LED50-RES)") (class "Default")
      (node (ref "LED50") (pin "2") (pinfunction "RES_2") (pintype "passive"))
      (node (ref "U8") (pin "9") (pinfunction "8B_9") (pintype "passive"))
    )
    (net (code "147") (name "Net-(LED51-RES)") (class "Default")
      (node (ref "LED51") (pin "2") (pinfunction "RES_2") (pintype "passive"))
      (node (ref "U9") (pin "9") (pinfunction "8B_9") (pintype "passive"))
    )
    (net (code "148") (name "Net-(LED52-RES)") (class "Default")
      (node (ref "LED52") (pin "2") (pinfunction "RES_2") (pintype "passive"))
      (node (ref "U10") (pin "9") (pinfunction "8B_9") (pintype "passive"))
    )
    (net (code "149") (name "Net-(LED53-RES)") (class "Default")
      (node (ref "LED53") (pin "2") (pinfunction "RES_2") (pintype "passive"))
      (node (ref "U11") (pin "9") (pinfunction "8B_9") (pintype "passive"))
    )
    (net (code "150") (name "Net-(LED54-RES)") (class "Default")
      (node (ref "LED54") (pin "2") (pinfunction "RES_2") (pintype "passive"))
      (node (ref "U12") (pin "9") (pinfunction "8B_9") (pintype "passive"))
    )
    (net (code "151") (name "Net-(LED55-RES)") (class "Default")
      (node (ref "LED55") (pin "2") (pinfunction "RES_2") (pintype "passive"))
      (node (ref "U13") (pin "9") (pinfunction "8B_9") (pintype "passive"))
    )
    (net (code "152") (name "Net-(LED56-A)") (class "Default")
      (node (ref "LED56") (pin "1") (pinfunction "A_1") (pintype "passive"))
      (node (ref "R19") (pin "1") (pinfunction "1_1") (pintype "passive"))
    )
    (net (code "153") (name "Net-(LED57-A)") (class "Default")
      (node (ref "LED57") (pin "1") (pinfunction "A_1") (pintype "passive"))
      (node (ref "R20") (pin "1") (pinfunction "1_1") (pintype "passive"))
    )
    (net (code "154") (name "Net-(LED58-A)") (class "Default")
      (node (ref "LED58") (pin "1") (pinfunction "A_1") (pintype "passive"))
      (node (ref "R21") (pin "1") (pinfunction "1_1") (pintype "passive"))
    )
    (net (code "155") (name "Net-(LED59-A)") (class "Default")
      (node (ref "LED59") (pin "1") (pinfunction "A_1") (pintype "passive"))
      (node (ref "R22") (pin "1") (pinfunction "1_1") (pintype "passive"))
    )
    (net (code "156") (name "Net-(LED60-A)") (class "Default")
      (node (ref "LED60") (pin "1") (pinfunction "A_1") (pintype "passive"))
      (node (ref "R23") (pin "1") (pinfunction "1_1") (pintype "passive"))
    )
    (net (code "157") (name "Net-(LED61-A)") (class "Default")
      (node (ref "LED61") (pin "1") (pinfunction "A_1") (pintype "passive"))
      (node (ref "R24") (pin "1") (pinfunction "1_1") (pintype "passive"))
    )
    (net (code "158") (name "Net-(LED62-A)") (class "Default")
      (node (ref "LED62") (pin "1") (pinfunction "A_1") (pintype "passive"))
      (node (ref "R25") (pin "1") (pinfunction "1_1") (pintype "passive"))
    )
    (net (code "159") (name "Net-(LED63-RES)") (class "Default")
      (node (ref "LED63") (pin "2") (pinfunction "RES_2") (pintype "passive"))
      (node (ref "U20") (pin "16") (pinfunction "1B_16") (pintype "passive"))
    )
    (net (code "160") (name "Net-(LED64-RES)") (class "Default")
      (node (ref "LED64") (pin "2") (pinfunction "RES_2") (pintype "passive"))
      (node (ref "U21") (pin "16") (pinfunction "1B_16") (pintype "passive"))
    )
    (net (code "161") (name "Net-(LED65-RES)") (class "Default")
      (node (ref "LED65") (pin "2") (pinfunction "RES_2") (pintype "passive"))
      (node (ref "U22") (pin "16") (pinfunction "1B_16") (pintype "passive"))
    )
    (net (code "162") (name "Net-(LED66-RES)") (class "Default")
      (node (ref "LED66") (pin "2") (pinfunction "RES_2") (pintype "passive"))
      (node (ref "U23") (pin "16") (pinfunction "1B_16") (pintype "passive"))
    )
    (net (code "163") (name "Net-(LED67-RES)") (class "Default")
      (node (ref "LED67") (pin "2") (pinfunction "RES_2") (pintype "passive"))
      (node (ref "U24") (pin "16") (pinfunction "1B_16") (pintype "passive"))
    )
    (net (code "164") (name "Net-(LED68-RES)") (class "Default")
      (node (ref "LED68") (pin "2") (pinfunction "RES_2") (pintype "passive"))
      (node (ref "U25") (pin "16") (pinfunction "1B_16") (pintype "passive"))
    )
    (net (code "165") (name "Net-(LED69-RES)") (class "Default")
      (node (ref "LED69") (pin "2") (pinfunction "RES_2") (pintype "passive"))
      (node (ref "U20") (pin "15") (pinfunction "2B_15") (pintype "passive"))
    )
    (net (code "166") (name "Net-(LED70-RES)") (class "Default")
      (node (ref "LED70") (pin "2") (pinfunction "RES_2") (pintype "passive"))
      (node (ref "U21") (pin "15") (pinfunction "2B_15") (pintype "passive"))
    )
    (net (code "167") (name "Net-(LED71-RES)") (class "Default")
      (node (ref "LED71") (pin "2") (pinfunction "RES_2") (pintype "passive"))
      (node (ref "U22") (pin "15") (pinfunction "2B_15") (pintype "passive"))
    )
    (net (code "168") (name "Net-(LED72-RES)") (class "Default")
      (node (ref "LED72") (pin "2") (pinfunction "RES_2") (pintype "passive"))
      (node (ref "U23") (pin "15") (pinfunction "2B_15") (pintype "passive"))
    )
    (net (code "169") (name "Net-(LED73-RES)") (class "Default")
      (node (ref "LED73") (pin "2") (pinfunction "RES_2") (pintype "passive"))
      (node (ref "U24") (pin "15") (pinfunction "2B_15") (pintype "passive"))
    )
    (net (code "170") (name "Net-(LED74-RES)") (class "Default")
      (node (ref "LED74") (pin "2") (pinfunction "RES_2") (pintype "passive"))
      (node (ref "U25") (pin "15") (pinfunction "2B_15") (pintype "passive"))
    )
    (net (code "171") (name "Net-(LED75-RES)") (class "Default")
      (node (ref "LED75") (pin "2") (pinfunction "RES_2") (pintype "passive"))
      (node (ref "U20") (pin "14") (pinfunction "3B_14") (pintype "passive"))
    )
    (net (code "172") (name "Net-(LED76-RES)") (class "Default")
      (node (ref "LED76") (pin "2") (pinfunction "RES_2") (pintype "passive"))
      (node (ref "U21") (pin "14") (pinfunction "3B_14") (pintype "passive"))
    )
    (net (code "173") (name "Net-(LED77-RES)") (class "Default")
      (node (ref "LED77") (pin "2") (pinfunction "RES_2") (pintype "passive"))
      (node (ref "U22") (pin "14") (pinfunction "3B_14") (pintype "passive"))
    )
    (net (code "174") (name "Net-(LED78-RES)") (class "Default")
      (node (ref "LED78") (pin "2") (pinfunction "RES_2") (pintype "passive"))
      (node (ref "U23") (pin "14") (pinfunction "3B_14") (pintype "passive"))
    )
    (net (code "175") (name "Net-(LED79-RES)") (class "Default")
      (node (ref "LED79") (pin "2") (pinfunction "RES_2") (pintype "passive"))
      (node (ref "U24") (pin "14") (pinfunction "3B_14") (pintype "passive"))
    )
    (net (code "176") (name "Net-(LED80-RES)") (class "Default")
      (node (ref "LED80") (pin "2") (pinfunction "RES_2") (pintype "passive"))
      (node (ref "U25") (pin "14") (pinfunction "3B_14") (pintype "passive"))
    )
    (net (code "177") (name "Net-(LED81-A)") (class "Default")
      (node (ref "LED81") (pin "1") (pinfunction "A_1") (pintype "passive"))
      (node (ref "R26") (pin "1") (pinfunction "1_1") (pintype "passive"))
    )
    (net (code "178") (name "Net-(LED82-RES)") (class "Default")
      (node (ref "LED82") (pin "2") (pinfunction "RES_2") (pintype "passive"))
      (node (ref "U20") (pin "13") (pinfunction "4B_13") (pintype "passive"))
    )
    (net (code "179") (name "Net-(LED83-RES)") (class "Default")
      (node (ref "LED83") (pin "2") (pinfunction "RES_2") (pintype "passive"))
      (node (ref "U21") (pin "13") (pinfunction "4B_13") (pintype "passive"))
    )
    (net (code "180") (name "Net-(LED84-RES)") (class "Default")
      (node (ref "LED84") (pin "2") (pinfunction "RES_2") (pintype "passive"))
      (node (ref "U22") (pin "13") (pinfunction "4B_13") (pintype "passive"))
    )
    (net (code "181") (name "Net-(LED85-RES)") (class "Default")
      (node (ref "LED85") (pin "2") (pinfunction "RES_2") (pintype "passive"))
      (node (ref "U23") (pin "13") (pinfunction "4B_13") (pintype "passive"))
    )
    (net (code "182") (name "Net-(LED86-RES)") (class "Default")
      (node (ref "LED86") (pin "2") (pinfunction "RES_2") (pintype "passive"))
      (node (ref "U24") (pin "13") (pinfunction "4B_13") (pintype "passive"))
    )
    (net (code "183") (name "Net-(LED87-RES)") (class "Default")
      (node (ref "LED87") (pin "2") (pinfunction "RES_2") (pintype "passive"))
      (node (ref "U25") (pin "13") (pinfunction "4B_13") (pintype "passive"))
    )
    (net (code "184") (name "Net-(LED88-RES)") (class "Default")
      (node (ref "LED88") (pin "2") (pinfunction "RES_2") (pintype "passive"))
      (node (ref "U20") (pin "12") (pinfunction "5B_12") (pintype "passive"))
    )
    (net (code "185") (name "Net-(LED89-RES)") (class "Default")
      (node (ref "LED89") (pin "2") (pinfunction "RES_2") (pintype "passive"))
      (node (ref "U21") (pin "12") (pinfunction "5B_12") (pintype "passive"))
    )
    (net (code "186") (name "Net-(LED90-RES)") (class "Default")
      (node (ref "LED90") (pin "2") (pinfunction "RES_2") (pintype "passive"))
      (node (ref "U22") (pin "12") (pinfunction "5B_12") (pintype "passive"))
    )
    (net (code "187") (name "Net-(LED91-RES)") (class "Default")
      (node (ref "LED91") (pin "2") (pinfunction "RES_2") (pintype "passive"))
      (node (ref "U23") (pin "12") (pinfunction "5B_12") (pintype "passive"))
    )
    (net (code "188") (name "Net-(LED92-RES)") (class "Default")
      (node (ref "LED92") (pin "2") (pinfunction "RES_2") (pintype "passive"))
      (node (ref "U24") (pin "12") (pinfunction "5B_12") (pintype "passive"))
    )
    (net (code "189") (name "Net-(LED93-RES)") (class "Default")
      (node (ref "LED93") (pin "2") (pinfunction "RES_2") (pintype "passive"))
      (node (ref "U25") (pin "12") (pinfunction "5B_12") (pintype "passive"))
    )
    (net (code "190") (name "Net-(LED94-RES)") (class "Default")
      (node (ref "LED94") (pin "2") (pinfunction "RES_2") (pintype "passive"))
      (node (ref "U20") (pin "11") (pinfunction "6B_11") (pintype "passive"))
    )
    (net (code "191") (name "Net-(LED95-RES)") (class "Default")
      (node (ref "LED95") (pin "2") (pinfunction "RES_2") (pintype "passive"))
      (node (ref "U21") (pin "11") (pinfunction "6B_11") (pintype "passive"))
    )
    (net (code "192") (name "Net-(LED96-RES)") (class "Default")
      (node (ref "LED96") (pin "2") (pinfunction "RES_2") (pintype "passive"))
      (node (ref "U22") (pin "11") (pinfunction "6B_11") (pintype "passive"))
    )
    (net (code "193") (name "Net-(LED97-RES)") (class "Default")
      (node (ref "LED97") (pin "2") (pinfunction "RES_2") (pintype "passive"))
      (node (ref "U23") (pin "11") (pinfunction "6B_11") (pintype "passive"))
    )
    (net (code "194") (name "Net-(LED98-RES)") (class "Default")
      (node (ref "LED98") (pin "2") (pinfunction "RES_2") (pintype "passive"))
      (node (ref "U24") (pin "11") (pinfunction "6B_11") (pintype "passive"))
    )
    (net (code "195") (name "Net-(LED99-RES)") (class "Default")
      (node (ref "LED99") (pin "2") (pinfunction "RES_2") (pintype "passive"))
      (node (ref "U25") (pin "11") (pinfunction "6B_11") (pintype "passive"))
    )
    (net (code "196") (name "Net-(LED100-A)") (class "Default")
      (node (ref "LED100") (pin "1") (pinfunction "A_1") (pintype "passive"))
      (node (ref "R27") (pin "1") (pinfunction "1_1") (pintype "passive"))
    )
    (net (code "197") (name "Net-(LED101-RES)") (class "Default")
      (node (ref "LED101") (pin "2") (pinfunction "RES_2") (pintype "passive"))
      (node (ref "U20") (pin "10") (pinfunction "7B_10") (pintype "passive"))
    )
    (net (code "198") (name "Net-(LED102-RES)") (class "Default")
      (node (ref "LED102") (pin "2") (pinfunction "RES_2") (pintype "passive"))
      (node (ref "U21") (pin "10") (pinfunction "7B_10") (pintype "passive"))
    )
    (net (code "199") (name "Net-(LED103-RES)") (class "Default")
      (node (ref "LED103") (pin "2") (pinfunction "RES_2") (pintype "passive"))
      (node (ref "U22") (pin "10") (pinfunction "7B_10") (pintype "passive"))
    )
    (net (code "200") (name "Net-(LED104-RES)") (class "Default")
      (node (ref "LED104") (pin "2") (pinfunction "RES_2") (pintype "passive"))
      (node (ref "U23") (pin "10") (pinfunction "7B_10") (pintype "passive"))
    )
    (net (code "201") (name "Net-(LED105-RES)") (class "Default")
      (node (ref "LED105") (pin "2") (pinfunction "RES_2") (pintype "passive"))
      (node (ref "U24") (pin "10") (pinfunction "7B_10") (pintype "passive"))
    )
    (net (code "202") (name "Net-(LED106-RES)") (class "Default")
      (node (ref "LED106") (pin "2") (pinfunction "RES_2") (pintype "passive"))
      (node (ref "U25") (pin "10") (pinfunction "7B_10") (pintype "passive"))
    )
    (net (code "203") (name "Net-(LED107-RES)") (class "Default")
      (node (ref "LED107") (pin "2") (pinfunction "RES_2") (pintype "passive"))
      (node (ref "U20") (pin "9") (pinfunction "8B_9") (pintype "passive"))
    )
    (net (code "204") (name "Net-(LED108-RES)") (class "Default")
      (node (ref "LED108") (pin "2") (pinfunction "RES_2") (pintype "passive"))
      (node (ref "U21") (pin "9") (pinfunction "8B_9") (pintype "passive"))
    )
    (net (code "205") (name "Net-(LED109-RES)") (class "Default")
      (node (ref "LED109") (pin "2") (pinfunction "RES_2") (pintype "passive"))
      (node (ref "U22") (pin "9") (pinfunction "8B_9") (pintype "passive"))
    )
    (net (code "206") (name "Net-(LED111-RES)") (class "Default")
      (node (ref "LED111") (pin "2") (pinfunction "RES_2") (pintype "passive"))
      (node (ref "U24") (pin "9") (pinfunction "8B_9") (pintype "passive"))
    )
    (net (code "207") (name "Net-(LED112-RES)") (class "Default")
      (node (ref "LED112") (pin "2") (pinfunction "RES_2") (pintype "passive"))
      (node (ref "U25") (pin "9") (pinfunction "8B_9") (pintype "passive"))
    )
    (net (code "208") (name "Net-(U2-Y1)") (class "Default")
      (node (ref "U2") (pin "18") (pinfunction "Y1_18") (pintype "tri_state"))
      (node (ref "U8") (pin "1") (pinfunction "1A_1") (pintype "passive"))
    )
    (net (code "209") (name "Net-(U2-Y2)") (class "Default")
      (node (ref "U2") (pin "17") (pinfunction "Y2_17") (pintype "tri_state"))
      (node (ref "U8") (pin "2") (pinfunction "2A_2") (pintype "passive"))
    )
    (net (code "210") (name "Net-(U2-Y3)") (class "Default")
      (node (ref "U2") (pin "16") (pinfunction "Y3_16") (pintype "tri_state"))
      (node (ref "U8") (pin "3") (pinfunction "3A_3") (pintype "passive"))
    )
    (net (code "211") (name "Net-(U2-Y4)") (class "Default")
      (node (ref "U2") (pin "15") (pinfunction "Y4_15") (pintype "tri_state"))
      (node (ref "U8") (pin "4") (pinfunction "4A_4") (pintype "passive"))
    )
    (net (code "212") (name "Net-(U2-Y5)") (class "Default")
      (node (ref "U2") (pin "14") (pinfunction "Y5_14") (pintype "tri_state"))
      (node (ref "U8") (pin "5") (pinfunction "5A_5") (pintype "passive"))
    )
    (net (code "213") (name "Net-(U2-Y6)") (class "Default")
      (node (ref "U2") (pin "13") (pinfunction "Y6_13") (pintype "tri_state"))
      (node (ref "U8") (pin "6") (pinfunction "6A_6") (pintype "passive"))
    )
    (net (code "214") (name "Net-(U2-Y7)") (class "Default")
      (node (ref "U2") (pin "12") (pinfunction "Y7_12") (pintype "tri_state"))
      (node (ref "U8") (pin "7") (pinfunction "7A_7") (pintype "passive"))
    )
    (net (code "215") (name "Net-(U2-Y8)") (class "Default")
      (node (ref "U2") (pin "11") (pinfunction "Y8_11") (pintype "tri_state"))
      (node (ref "U8") (pin "8") (pinfunction "8A_8") (pintype "passive"))
    )
    (net (code "216") (name "Net-(U3-Y1)") (class "Default")
      (node (ref "U3") (pin "18") (pinfunction "Y1_18") (pintype "tri_state"))
      (node (ref "U9") (pin "1") (pinfunction "1A_1") (pintype "passive"))
    )
    (net (code "217") (name "Net-(U3-Y2)") (class "Default")
      (node (ref "U3") (pin "17") (pinfunction "Y2_17") (pintype "tri_state"))
      (node (ref "U9") (pin "2") (pinfunction "2A_2") (pintype "passive"))
    )
    (net (code "218") (name "Net-(U3-Y3)") (class "Default")
      (node (ref "U3") (pin "16") (pinfunction "Y3_16") (pintype "tri_state"))
      (node (ref "U9") (pin "3") (pinfunction "3A_3") (pintype "passive"))
    )
    (net (code "219") (name "Net-(U3-Y4)") (class "Default")
      (node (ref "U3") (pin "15") (pinfunction "Y4_15") (pintype "tri_state"))
      (node (ref "U9") (pin "4") (pinfunction "4A_4") (pintype "passive"))
    )
    (net (code "220") (name "Net-(U3-Y5)") (class "Default")
      (node (ref "U3") (pin "14") (pinfunction "Y5_14") (pintype "tri_state"))
      (node (ref "U9") (pin "5") (pinfunction "5A_5") (pintype "passive"))
    )
    (net (code "221") (name "Net-(U3-Y6)") (class "Default")
      (node (ref "U3") (pin "13") (pinfunction "Y6_13") (pintype "tri_state"))
      (node (ref "U9") (pin "6") (pinfunction "6A_6") (pintype "passive"))
    )
    (net (code "222") (name "Net-(U3-Y7)") (class "Default")
      (node (ref "U3") (pin "12") (pinfunction "Y7_12") (pintype "tri_state"))
      (node (ref "U9") (pin "7") (pinfunction "7A_7") (pintype "passive"))
    )
    (net (code "223") (name "Net-(U3-Y8)") (class "Default")
      (node (ref "U3") (pin "11") (pinfunction "Y8_11") (pintype "tri_state"))
      (node (ref "U9") (pin "8") (pinfunction "8A_8") (pintype "passive"))
    )
    (net (code "224") (name "Net-(U10-1A)") (class "Default")
      (node (ref "U10") (pin "1") (pinfunction "1A_1") (pintype "passive"))
      (node (ref "U4") (pin "18") (pinfunction "Y1_18") (pintype "tri_state"))
    )
    (net (code "225") (name "Net-(U10-2A)") (class "Default")
      (node (ref "U10") (pin "2") (pinfunction "2A_2") (pintype "passive"))
      (node (ref "U4") (pin "17") (pinfunction "Y2_17") (pintype "tri_state"))
    )
    (net (code "226") (name "Net-(U10-3A)") (class "Default")
      (node (ref "U10") (pin "3") (pinfunction "3A_3") (pintype "passive"))
      (node (ref "U4") (pin "16") (pinfunction "Y3_16") (pintype "tri_state"))
    )
    (net (code "227") (name "Net-(U10-4A)") (class "Default")
      (node (ref "U10") (pin "4") (pinfunction "4A_4") (pintype "passive"))
      (node (ref "U4") (pin "15") (pinfunction "Y4_15") (pintype "tri_state"))
    )
    (net (code "228") (name "Net-(U10-5A)") (class "Default")
      (node (ref "U10") (pin "5") (pinfunction "5A_5") (pintype "passive"))
      (node (ref "U4") (pin "14") (pinfunction "Y5_14") (pintype "tri_state"))
    )
    (net (code "229") (name "Net-(U10-6A)") (class "Default")
      (node (ref "U10") (pin "6") (pinfunction "6A_6") (pintype "passive"))
      (node (ref "U4") (pin "13") (pinfunction "Y6_13") (pintype "tri_state"))
    )
    (net (code "230") (name "Net-(U10-7A)") (class "Default")
      (node (ref "U10") (pin "7") (pinfunction "7A_7") (pintype "passive"))
      (node (ref "U4") (pin "12") (pinfunction "Y7_12") (pintype "tri_state"))
    )
    (net (code "231") (name "Net-(U10-8A)") (class "Default")
      (node (ref "U10") (pin "8") (pinfunction "8A_8") (pintype "passive"))
      (node (ref "U4") (pin "11") (pinfunction "Y8_11") (pintype "tri_state"))
    )
    (net (code "232") (name "Net-(U11-1A)") (class "Default")
      (node (ref "U11") (pin "1") (pinfunction "1A_1") (pintype "passive"))
      (node (ref "U5") (pin "18") (pinfunction "Y1_18") (pintype "tri_state"))
    )
    (net (code "233") (name "Net-(U11-2A)") (class "Default")
      (node (ref "U11") (pin "2") (pinfunction "2A_2") (pintype "passive"))
      (node (ref "U5") (pin "17") (pinfunction "Y2_17") (pintype "tri_state"))
    )
    (net (code "234") (name "Net-(U11-3A)") (class "Default")
      (node (ref "U11") (pin "3") (pinfunction "3A_3") (pintype "passive"))
      (node (ref "U5") (pin "16") (pinfunction "Y3_16") (pintype "tri_state"))
    )
    (net (code "235") (name "Net-(U11-4A)") (class "Default")
      (node (ref "U11") (pin "4") (pinfunction "4A_4") (pintype "passive"))
      (node (ref "U5") (pin "15") (pinfunction "Y4_15") (pintype "tri_state"))
    )
    (net (code "236") (name "Net-(U11-5A)") (class "Default")
      (node (ref "U11") (pin "5") (pinfunction "5A_5") (pintype "passive"))
      (node (ref "U5") (pin "14") (pinfunction "Y5_14") (pintype "tri_state"))
    )
    (net (code "237") (name "Net-(U11-6A)") (class "Default")
      (node (ref "U11") (pin "6") (pinfunction "6A_6") (pintype "passive"))
      (node (ref "U5") (pin "13") (pinfunction "Y6_13") (pintype "tri_state"))
    )
    (net (code "238") (name "Net-(U11-7A)") (class "Default")
      (node (ref "U11") (pin "7") (pinfunction "7A_7") (pintype "passive"))
      (node (ref "U5") (pin "12") (pinfunction "Y7_12") (pintype "tri_state"))
    )
    (net (code "239") (name "Net-(U11-8A)") (class "Default")
      (node (ref "U11") (pin "8") (pinfunction "8A_8") (pintype "passive"))
      (node (ref "U5") (pin "11") (pinfunction "Y8_11") (pintype "tri_state"))
    )
    (net (code "240") (name "Net-(U12-1A)") (class "Default")
      (node (ref "U12") (pin "1") (pinfunction "1A_1") (pintype "passive"))
      (node (ref "U6") (pin "18") (pinfunction "Y1_18") (pintype "tri_state"))
    )
    (net (code "241") (name "Net-(U12-2A)") (class "Default")
      (node (ref "U12") (pin "2") (pinfunction "2A_2") (pintype "passive"))
      (node (ref "U6") (pin "17") (pinfunction "Y2_17") (pintype "tri_state"))
    )
    (net (code "242") (name "Net-(U12-3A)") (class "Default")
      (node (ref "U12") (pin "3") (pinfunction "3A_3") (pintype "passive"))
      (node (ref "U6") (pin "16") (pinfunction "Y3_16") (pintype "tri_state"))
    )
    (net (code "243") (name "Net-(U12-4A)") (class "Default")
      (node (ref "U12") (pin "4") (pinfunction "4A_4") (pintype "passive"))
      (node (ref "U6") (pin "15") (pinfunction "Y4_15") (pintype "tri_state"))
    )
    (net (code "244") (name "Net-(U12-5A)") (class "Default")
      (node (ref "U12") (pin "5") (pinfunction "5A_5") (pintype "passive"))
      (node (ref "U6") (pin "14") (pinfunction "Y5_14") (pintype "tri_state"))
    )
    (net (code "245") (name "Net-(U12-6A)") (class "Default")
      (node (ref "U12") (pin "6") (pinfunction "6A_6") (pintype "passive"))
      (node (ref "U6") (pin "13") (pinfunction "Y6_13") (pintype "tri_state"))
    )
    (net (code "246") (name "Net-(U12-7A)") (class "Default")
      (node (ref "U12") (pin "7") (pinfunction "7A_7") (pintype "passive"))
      (node (ref "U6") (pin "12") (pinfunction "Y7_12") (pintype "tri_state"))
    )
    (net (code "247") (name "Net-(U12-8A)") (class "Default")
      (node (ref "U12") (pin "8") (pinfunction "8A_8") (pintype "passive"))
      (node (ref "U6") (pin "11") (pinfunction "Y8_11") (pintype "tri_state"))
    )
    (net (code "248") (name "Net-(U13-1A)") (class "Default")
      (node (ref "U13") (pin "1") (pinfunction "1A_1") (pintype "passive"))
      (node (ref "U7") (pin "18") (pinfunction "Y1_18") (pintype "tri_state"))
    )
    (net (code "249") (name "Net-(U13-2A)") (class "Default")
      (node (ref "U13") (pin "2") (pinfunction "2A_2") (pintype "passive"))
      (node (ref "U7") (pin "17") (pinfunction "Y2_17") (pintype "tri_state"))
    )
    (net (code "250") (name "Net-(U13-3A)") (class "Default")
      (node (ref "U13") (pin "3") (pinfunction "3A_3") (pintype "passive"))
      (node (ref "U7") (pin "16") (pinfunction "Y3_16") (pintype "tri_state"))
    )
    (net (code "251") (name "Net-(U13-4A)") (class "Default")
      (node (ref "U13") (pin "4") (pinfunction "4A_4") (pintype "passive"))
      (node (ref "U7") (pin "15") (pinfunction "Y4_15") (pintype "tri_state"))
    )
    (net (code "252") (name "Net-(U13-5A)") (class "Default")
      (node (ref "U13") (pin "5") (pinfunction "5A_5") (pintype "passive"))
      (node (ref "U7") (pin "14") (pinfunction "Y5_14") (pintype "tri_state"))
    )
    (net (code "253") (name "Net-(U13-6A)") (class "Default")
      (node (ref "U13") (pin "6") (pinfunction "6A_6") (pintype "passive"))
      (node (ref "U7") (pin "13") (pinfunction "Y6_13") (pintype "tri_state"))
    )
    (net (code "254") (name "Net-(U13-7A)") (class "Default")
      (node (ref "U13") (pin "7") (pinfunction "7A_7") (pintype "passive"))
      (node (ref "U7") (pin "12") (pinfunction "Y7_12") (pintype "tri_state"))
    )
    (net (code "255") (name "Net-(U13-8A)") (class "Default")
      (node (ref "U13") (pin "8") (pinfunction "8A_8") (pintype "passive"))
      (node (ref "U7") (pin "11") (pinfunction "Y8_11") (pintype "tri_state"))
    )
    (net (code "256") (name "Net-(U14-Y1)") (class "Default")
      (node (ref "U14") (pin "18") (pinfunction "Y1_18") (pintype "tri_state"))
      (node (ref "U20") (pin "1") (pinfunction "1A_1") (pintype "passive"))
    )
    (net (code "257") (name "Net-(U14-Y2)") (class "Default")
      (node (ref "U14") (pin "17") (pinfunction "Y2_17") (pintype "tri_state"))
      (node (ref "U20") (pin "2") (pinfunction "2A_2") (pintype "passive"))
    )
    (net (code "258") (name "Net-(U14-Y3)") (class "Default")
      (node (ref "U14") (pin "16") (pinfunction "Y3_16") (pintype "tri_state"))
      (node (ref "U20") (pin "3") (pinfunction "3A_3") (pintype "passive"))
    )
    (net (code "259") (name "Net-(U14-Y4)") (class "Default")
      (node (ref "U14") (pin "15") (pinfunction "Y4_15") (pintype "tri_state"))
      (node (ref "U20") (pin "4") (pinfunction "4A_4") (pintype "passive"))
    )
    (net (code "260") (name "Net-(U14-Y5)") (class "Default")
      (node (ref "U14") (pin "14") (pinfunction "Y5_14") (pintype "tri_state"))
      (node (ref "U20") (pin "5") (pinfunction "5A_5") (pintype "passive"))
    )
    (net (code "261") (name "Net-(U14-Y6)") (class "Default")
      (node (ref "U14") (pin "13") (pinfunction "Y6_13") (pintype "tri_state"))
      (node (ref "U20") (pin "6") (pinfunction "6A_6") (pintype "passive"))
    )
    (net (code "262") (name "Net-(U14-Y7)") (class "Default")
      (node (ref "U14") (pin "12") (pinfunction "Y7_12") (pintype "tri_state"))
      (node (ref "U20") (pin "7") (pinfunction "7A_7") (pintype "passive"))
    )
    (net (code "263") (name "Net-(U14-Y8)") (class "Default")
      (node (ref "U14") (pin "11") (pinfunction "Y8_11") (pintype "tri_state"))
      (node (ref "U20") (pin "8") (pinfunction "8A_8") (pintype "passive"))
    )
    (net (code "264") (name "Net-(U15-Y1)") (class "Default")
      (node (ref "U15") (pin "18") (pinfunction "Y1_18") (pintype "tri_state"))
      (node (ref "U21") (pin "1") (pinfunction "1A_1") (pintype "passive"))
    )
    (net (code "265") (name "Net-(U15-Y2)") (class "Default")
      (node (ref "U15") (pin "17") (pinfunction "Y2_17") (pintype "tri_state"))
      (node (ref "U21") (pin "2") (pinfunction "2A_2") (pintype "passive"))
    )
    (net (code "266") (name "Net-(U15-Y3)") (class "Default")
      (node (ref "U15") (pin "16") (pinfunction "Y3_16") (pintype "tri_state"))
      (node (ref "U21") (pin "3") (pinfunction "3A_3") (pintype "passive"))
    )
    (net (code "267") (name "Net-(U15-Y4)") (class "Default")
      (node (ref "U15") (pin "15") (pinfunction "Y4_15") (pintype "tri_state"))
      (node (ref "U21") (pin "4") (pinfunction "4A_4") (pintype "passive"))
    )
    (net (code "268") (name "Net-(U15-Y5)") (class "Default")
      (node (ref "U15") (pin "14") (pinfunction "Y5_14") (pintype "tri_state"))
      (node (ref "U21") (pin "5") (pinfunction "5A_5") (pintype "passive"))
    )
    (net (code "269") (name "Net-(U15-Y6)") (class "Default")
      (node (ref "U15") (pin "13") (pinfunction "Y6_13") (pintype "tri_state"))
      (node (ref "U21") (pin "6") (pinfunction "6A_6") (pintype "passive"))
    )
    (net (code "270") (name "Net-(U15-Y7)") (class "Default")
      (node (ref "U15") (pin "12") (pinfunction "Y7_12") (pintype "tri_state"))
      (node (ref "U21") (pin "7") (pinfunction "7A_7") (pintype "passive"))
    )
    (net (code "271") (name "Net-(U15-Y8)") (class "Default")
      (node (ref "U15") (pin "11") (pinfunction "Y8_11") (pintype "tri_state"))
      (node (ref "U21") (pin "8") (pinfunction "8A_8") (pintype "passive"))
    )
    (net (code "272") (name "Net-(U16-Y1)") (class "Default")
      (node (ref "U16") (pin "18") (pinfunction "Y1_18") (pintype "tri_state"))
      (node (ref "U22") (pin "1") (pinfunction "1A_1") (pintype "passive"))
    )
    (net (code "273") (name "Net-(U16-Y2)") (class "Default")
      (node (ref "U16") (pin "17") (pinfunction "Y2_17") (pintype "tri_state"))
      (node (ref "U22") (pin "2") (pinfunction "2A_2") (pintype "passive"))
    )
    (net (code "274") (name "Net-(U16-Y3)") (class "Default")
      (node (ref "U16") (pin "16") (pinfunction "Y3_16") (pintype "tri_state"))
      (node (ref "U22") (pin "3") (pinfunction "3A_3") (pintype "passive"))
    )
    (net (code "275") (name "Net-(U16-Y4)") (class "Default")
      (node (ref "U16") (pin "15") (pinfunction "Y4_15") (pintype "tri_state"))
      (node (ref "U22") (pin "4") (pinfunction "4A_4") (pintype "passive"))
    )
    (net (code "276") (name "Net-(U16-Y5)") (class "Default")
      (node (ref "U16") (pin "14") (pinfunction "Y5_14") (pintype "tri_state"))
      (node (ref "U22") (pin "5") (pinfunction "5A_5") (pintype "passive"))
    )
    (net (code "277") (name "Net-(U16-Y6)") (class "Default")
      (node (ref "U16") (pin "13") (pinfunction "Y6_13") (pintype "tri_state"))
      (node (ref "U22") (pin "6") (pinfunction "6A_6") (pintype "passive"))
    )
    (net (code "278") (name "Net-(U16-Y7)") (class "Default")
      (node (ref "U16") (pin "12") (pinfunction "Y7_12") (pintype "tri_state"))
      (node (ref "U22") (pin "7") (pinfunction "7A_7") (pintype "passive"))
    )
    (net (code "279") (name "Net-(U16-Y8)") (class "Default")
      (node (ref "U16") (pin "11") (pinfunction "Y8_11") (pintype "tri_state"))
      (node (ref "U22") (pin "8") (pinfunction "8A_8") (pintype "passive"))
    )
    (net (code "280") (name "Net-(U17-Y1)") (class "Default")
      (node (ref "U17") (pin "18") (pinfunction "Y1_18") (pintype "tri_state"))
      (node (ref "U23") (pin "1") (pinfunction "1A_1") (pintype "passive"))
    )
    (net (code "281") (name "Net-(U17-Y2)") (class "Default")
      (node (ref "U17") (pin "17") (pinfunction "Y2_17") (pintype "tri_state"))
      (node (ref "U23") (pin "2") (pinfunction "2A_2") (pintype "passive"))
    )
    (net (code "282") (name "Net-(U17-Y3)") (class "Default")
      (node (ref "U17") (pin "16") (pinfunction "Y3_16") (pintype "tri_state"))
      (node (ref "U23") (pin "3") (pinfunction "3A_3") (pintype "passive"))
    )
    (net (code "283") (name "Net-(U17-Y4)") (class "Default")
      (node (ref "U17") (pin "15") (pinfunction "Y4_15") (pintype "tri_state"))
      (node (ref "U23") (pin "4") (pinfunction "4A_4") (pintype "passive"))
    )
    (net (code "284") (name "Net-(U17-Y5)") (class "Default")
      (node (ref "U17") (pin "14") (pinfunction "Y5_14") (pintype "tri_state"))
      (node (ref "U23") (pin "5") (pinfunction "5A_5") (pintype "passive"))
    )
    (net (code "285") (name "Net-(U17-Y6)") (class "Default")
      (node (ref "U17") (pin "13") (pinfunction "Y6_13") (pintype "tri_state"))
      (node (ref "U23") (pin "6") (pinfunction "6A_6") (pintype "passive"))
    )
    (net (code "286") (name "Net-(U17-Y7)") (class "Default")
      (node (ref "U17") (pin "12") (pinfunction "Y7_12") (pintype "tri_state"))
      (node (ref "U23") (pin "7") (pinfunction "7A_7") (pintype "passive"))
    )
    (net (code "287") (name "Net-(U17-Y8)") (class "Default")
      (node (ref "U17") (pin "11") (pinfunction "Y8_11") (pintype "tri_state"))
      (node (ref "U23") (pin "8") (pinfunction "8A_8") (pintype "passive"))
    )
    (net (code "288") (name "Net-(U18-A1)") (class "Default")
      (node (ref "J35") (pin "1") (pinfunction "1_1") (pintype "passive"))
      (node (ref "U18") (pin "2") (pinfunction "A1_2") (pintype "input"))
    )
    (net (code "289") (name "Net-(U18-A2)") (class "Default")
      (node (ref "J35") (pin "2") (pinfunction "2_2") (pintype "passive"))
      (node (ref "U18") (pin "3") (pinfunction "A2_3") (pintype "input"))
    )
    (net (code "290") (name "Net-(U18-A3)") (class "Default")
      (node (ref "J35") (pin "3") (pinfunction "3_3") (pintype "passive"))
      (node (ref "U18") (pin "4") (pinfunction "A3_4") (pintype "input"))
    )
    (net (code "291") (name "Net-(U18-A4)") (class "Default")
      (node (ref "J35") (pin "4") (pinfunction "4_4") (pintype "passive"))
      (node (ref "U18") (pin "5") (pinfunction "A4_5") (pintype "input"))
    )
    (net (code "292") (name "Net-(U18-A5)") (class "Default")
      (node (ref "J35") (pin "5") (pinfunction "5_5") (pintype "passive"))
      (node (ref "U18") (pin "6") (pinfunction "A5_6") (pintype "input"))
    )
    (net (code "293") (name "Net-(U18-A6)") (class "Default")
      (node (ref "J35") (pin "6") (pinfunction "6_6") (pintype "passive"))
      (node (ref "U18") (pin "7") (pinfunction "A6_7") (pintype "input"))
    )
    (net (code "294") (name "Net-(U18-A7)") (class "Default")
      (node (ref "J35") (pin "7") (pinfunction "7_7") (pintype "passive"))
      (node (ref "U18") (pin "8") (pinfunction "A7_8") (pintype "input"))
    )
    (net (code "295") (name "Net-(U18-A8)") (class "Default")
      (node (ref "J35") (pin "8") (pinfunction "8_8") (pintype "passive"))
      (node (ref "U18") (pin "9") (pinfunction "A8_9") (pintype "input"))
    )
    (net (code "296") (name "Net-(U18-Y1)") (class "Default")
      (node (ref "U18") (pin "18") (pinfunction "Y1_18") (pintype "tri_state"))
      (node (ref "U24") (pin "1") (pinfunction "1A_1") (pintype "passive"))
    )
    (net (code "297") (name "Net-(U18-Y2)") (class "Default")
      (node (ref "U18") (pin "17") (pinfunction "Y2_17") (pintype "tri_state"))
      (node (ref "U24") (pin "2") (pinfunction "2A_2") (pintype "passive"))
    )
    (net (code "298") (name "Net-(U18-Y3)") (class "Default")
      (node (ref "U18") (pin "16") (pinfunction "Y3_16") (pintype "tri_state"))
      (node (ref "U24") (pin "3") (pinfunction "3A_3") (pintype "passive"))
    )
    (net (code "299") (name "Net-(U18-Y4)") (class "Default")
      (node (ref "U18") (pin "15") (pinfunction "Y4_15") (pintype "tri_state"))
      (node (ref "U24") (pin "4") (pinfunction "4A_4") (pintype "passive"))
    )
    (net (code "300") (name "Net-(U18-Y5)") (class "Default")
      (node (ref "U18") (pin "14") (pinfunction "Y5_14") (pintype "tri_state"))
      (node (ref "U24") (pin "5") (pinfunction "5A_5") (pintype "passive"))
    )
    (net (code "301") (name "Net-(U18-Y6)") (class "Default")
      (node (ref "U18") (pin "13") (pinfunction "Y6_13") (pintype "tri_state"))
      (node (ref "U24") (pin "6") (pinfunction "6A_6") (pintype "passive"))
    )
    (net (code "302") (name "Net-(U18-Y7)") (class "Default")
      (node (ref "U18") (pin "12") (pinfunction "Y7_12") (pintype "tri_state"))
      (node (ref "U24") (pin "7") (pinfunction "7A_7") (pintype "passive"))
    )
    (net (code "303") (name "Net-(U18-Y8)") (class "Default")
      (node (ref "U18") (pin "11") (pinfunction "Y8_11") (pintype "tri_state"))
      (node (ref "U24") (pin "8") (pinfunction "8A_8") (pintype "passive"))
    )
    (net (code "304") (name "Net-(U19-A1)") (class "Default")
      (node (ref "J36") (pin "1") (pinfunction "1_1") (pintype "passive"))
      (node (ref "U19") (pin "2") (pinfunction "A1_2") (pintype "input"))
    )
    (net (code "305") (name "Net-(U19-A2)") (class "Default")
      (node (ref "J36") (pin "2") (pinfunction "2_2") (pintype "passive"))
      (node (ref "U19") (pin "3") (pinfunction "A2_3") (pintype "input"))
    )
    (net (code "306") (name "Net-(U19-A3)") (class "Default")
      (node (ref "J36") (pin "3") (pinfunction "3_3") (pintype "passive"))
      (node (ref "U19") (pin "4") (pinfunction "A3_4") (pintype "input"))
    )
    (net (code "307") (name "Net-(U19-A4)") (class "Default")
      (node (ref "J36") (pin "4") (pinfunction "4_4") (pintype "passive"))
      (node (ref "U19") (pin "5") (pinfunction "A4_5") (pintype "input"))
    )
    (net (code "308") (name "Net-(U19-A5)") (class "Default")
      (node (ref "J36") (pin "5") (pinfunction "5_5") (pintype "passive"))
      (node (ref "U19") (pin "6") (pinfunction "A5_6") (pintype "input"))
    )
    (net (code "309") (name "Net-(U19-A6)") (class "Default")
      (node (ref "J36") (pin "6") (pinfunction "6_6") (pintype "passive"))
      (node (ref "U19") (pin "7") (pinfunction "A6_7") (pintype "input"))
    )
    (net (code "310") (name "Net-(U19-A7)") (class "Default")
      (node (ref "J36") (pin "7") (pinfunction "7_7") (pintype "passive"))
      (node (ref "U19") (pin "8") (pinfunction "A7_8") (pintype "input"))
    )
    (net (code "311") (name "Net-(U19-A8)") (class "Default")
      (node (ref "J36") (pin "8") (pinfunction "8_8") (pintype "passive"))
      (node (ref "U19") (pin "9") (pinfunction "A8_9") (pintype "input"))
    )
    (net (code "312") (name "Net-(U19-Y1)") (class "Default")
      (node (ref "U19") (pin "18") (pinfunction "Y1_18") (pintype "tri_state"))
      (node (ref "U25") (pin "1") (pinfunction "1A_1") (pintype "passive"))
    )
    (net (code "313") (name "Net-(U19-Y2)") (class "Default")
      (node (ref "U19") (pin "17") (pinfunction "Y2_17") (pintype "tri_state"))
      (node (ref "U25") (pin "2") (pinfunction "2A_2") (pintype "passive"))
    )
    (net (code "314") (name "Net-(U19-Y3)") (class "Default")
      (node (ref "U19") (pin "16") (pinfunction "Y3_16") (pintype "tri_state"))
      (node (ref "U25") (pin "3") (pinfunction "3A_3") (pintype "passive"))
    )
    (net (code "315") (name "Net-(U19-Y4)") (class "Default")
      (node (ref "U19") (pin "15") (pinfunction "Y4_15") (pintype "tri_state"))
      (node (ref "U25") (pin "4") (pinfunction "4A_4") (pintype "passive"))
    )
    (net (code "316") (name "Net-(U19-Y5)") (class "Default")
      (node (ref "U19") (pin "14") (pinfunction "Y5_14") (pintype "tri_state"))
      (node (ref "U25") (pin "5") (pinfunction "5A_5") (pintype "passive"))
    )
    (net (code "317") (name "Net-(U19-Y6)") (class "Default")
      (node (ref "U19") (pin "13") (pinfunction "Y6_13") (pintype "tri_state"))
      (node (ref "U25") (pin "6") (pinfunction "6A_6") (pintype "passive"))
    )
    (net (code "318") (name "Net-(U19-Y7)") (class "Default")
      (node (ref "U19") (pin "12") (pinfunction "Y7_12") (pintype "tri_state"))
      (node (ref "U25") (pin "7") (pinfunction "7A_7") (pintype "passive"))
    )
    (net (code "319") (name "Net-(U19-Y8)") (class "Default")
      (node (ref "U19") (pin "11") (pinfunction "Y8_11") (pintype "tri_state"))
      (node (ref "U25") (pin "8") (pinfunction "8A_8") (pintype "passive"))
    )
    (net (code "320") (name "unconnected-(U17-A8-Pad9)") (class "Default")
      (node (ref "U17") (pin "9") (pinfunction "A8_9") (pintype "input+no_connect"))
    )
    (net (code "321") (name "unconnected-(U19-GND-Pad10)") (class "Default")
      (node (ref "U19") (pin "10") (pinfunction "GND_10") (pintype "power_in"))
    )
    (net (code "322") (name "unconnected-(U23-8B-Pad9)") (class "Default")
      (node (ref "U23") (pin "9") (pinfunction "8B_9") (pintype "passive+no_connect"))
    )
  )
)
